# DrumPad.net
KiCad netlist of a schematic drawn in Altium Designer
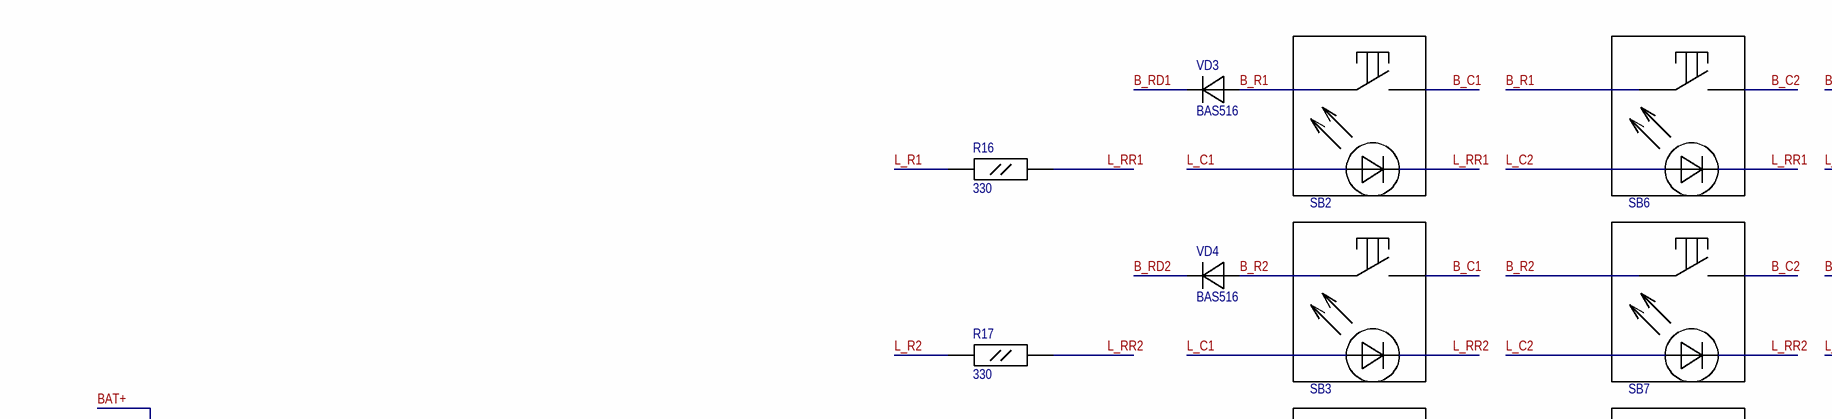
[diagram p0: DrumPad.SchDoc, top left]
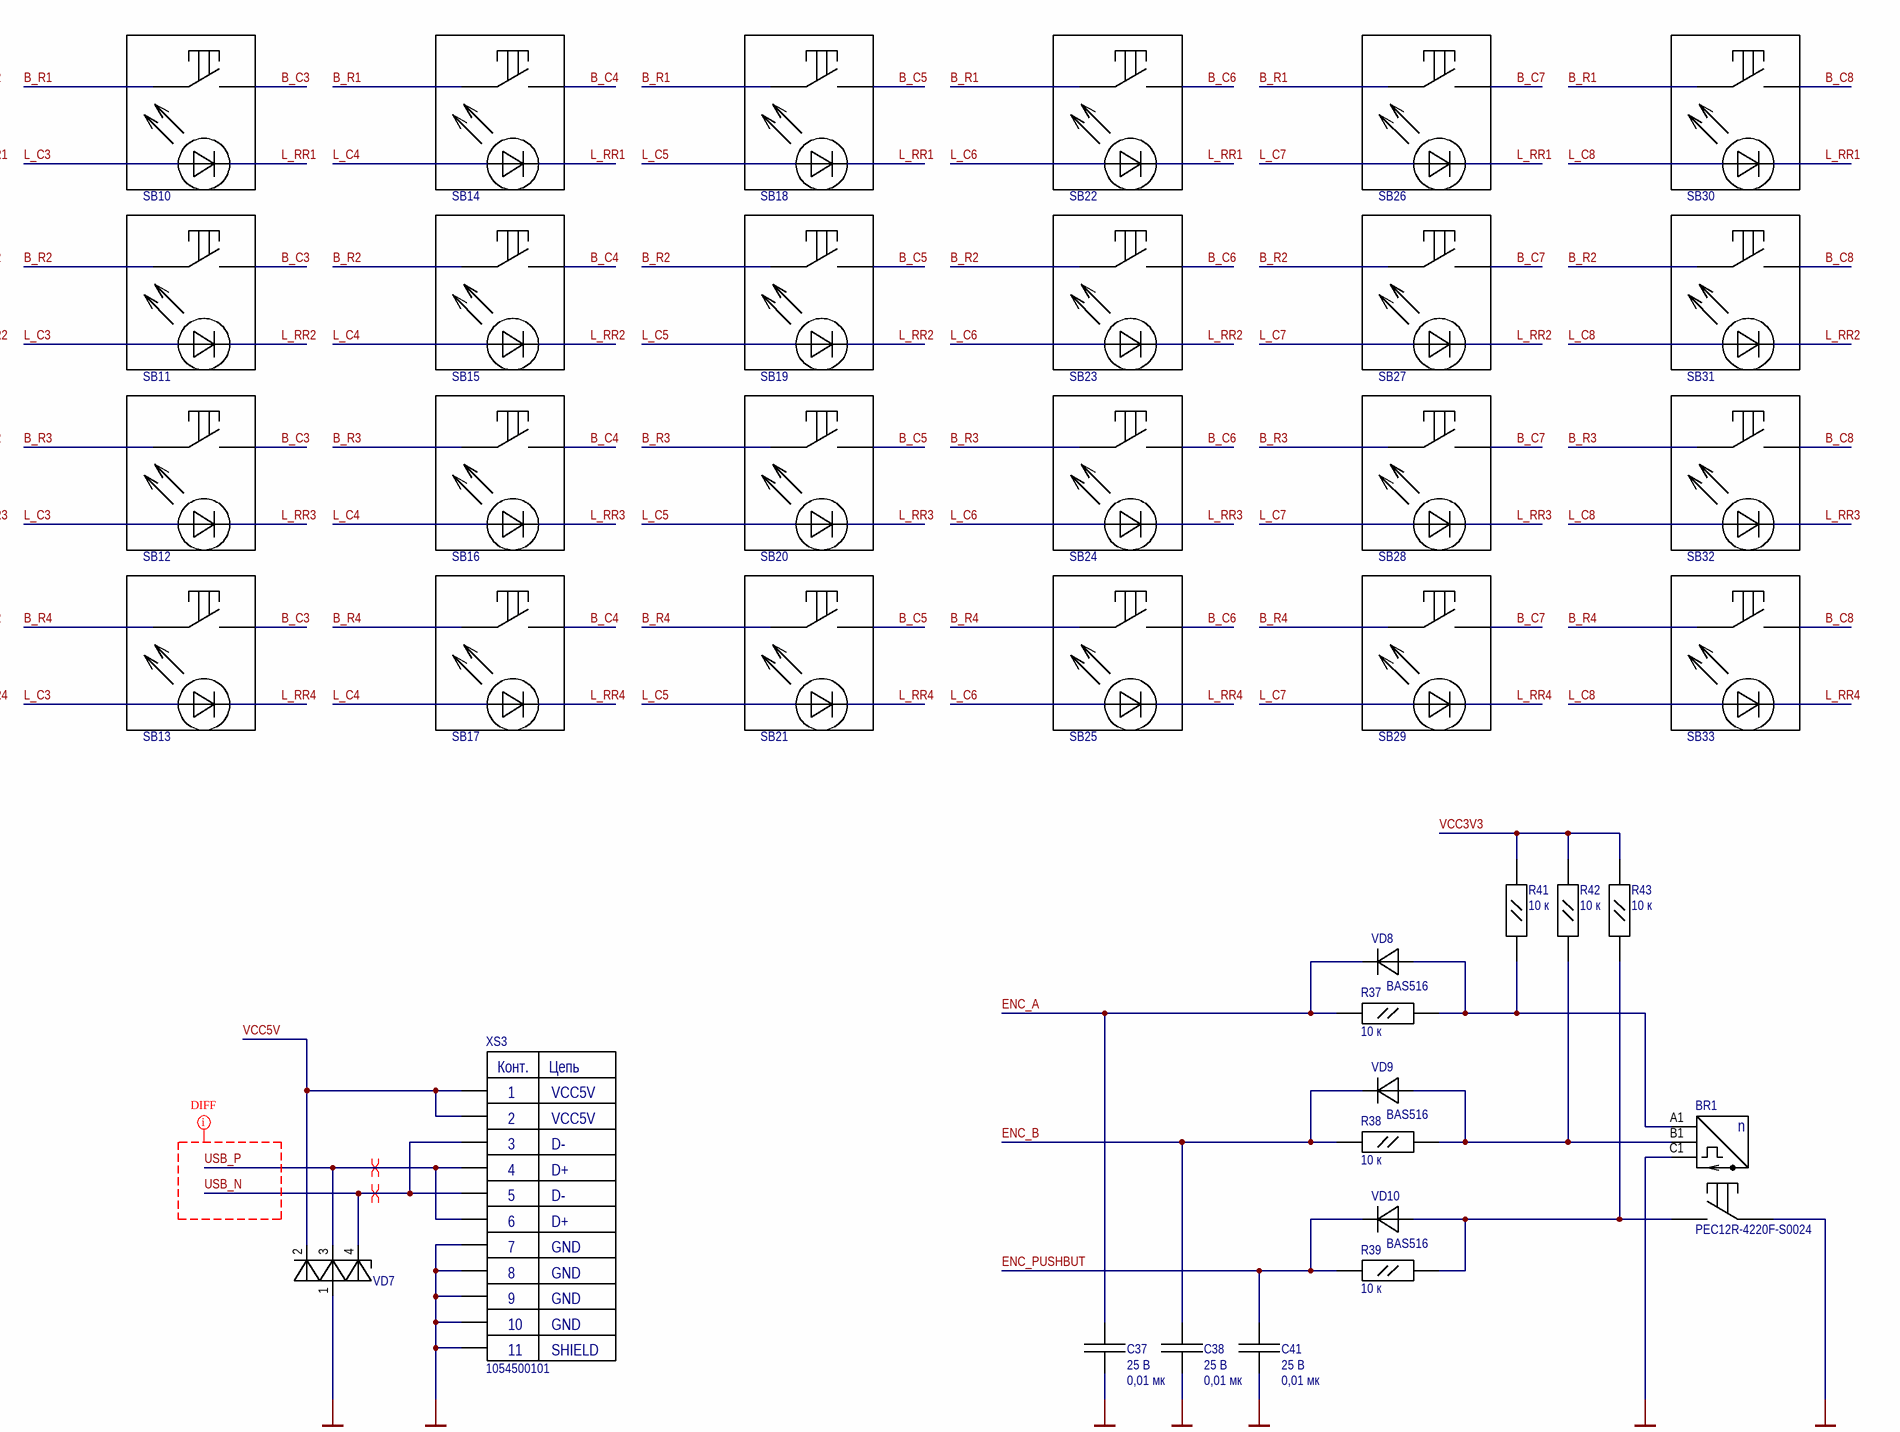
[diagram p1: DrumPad.SchDoc, top right]
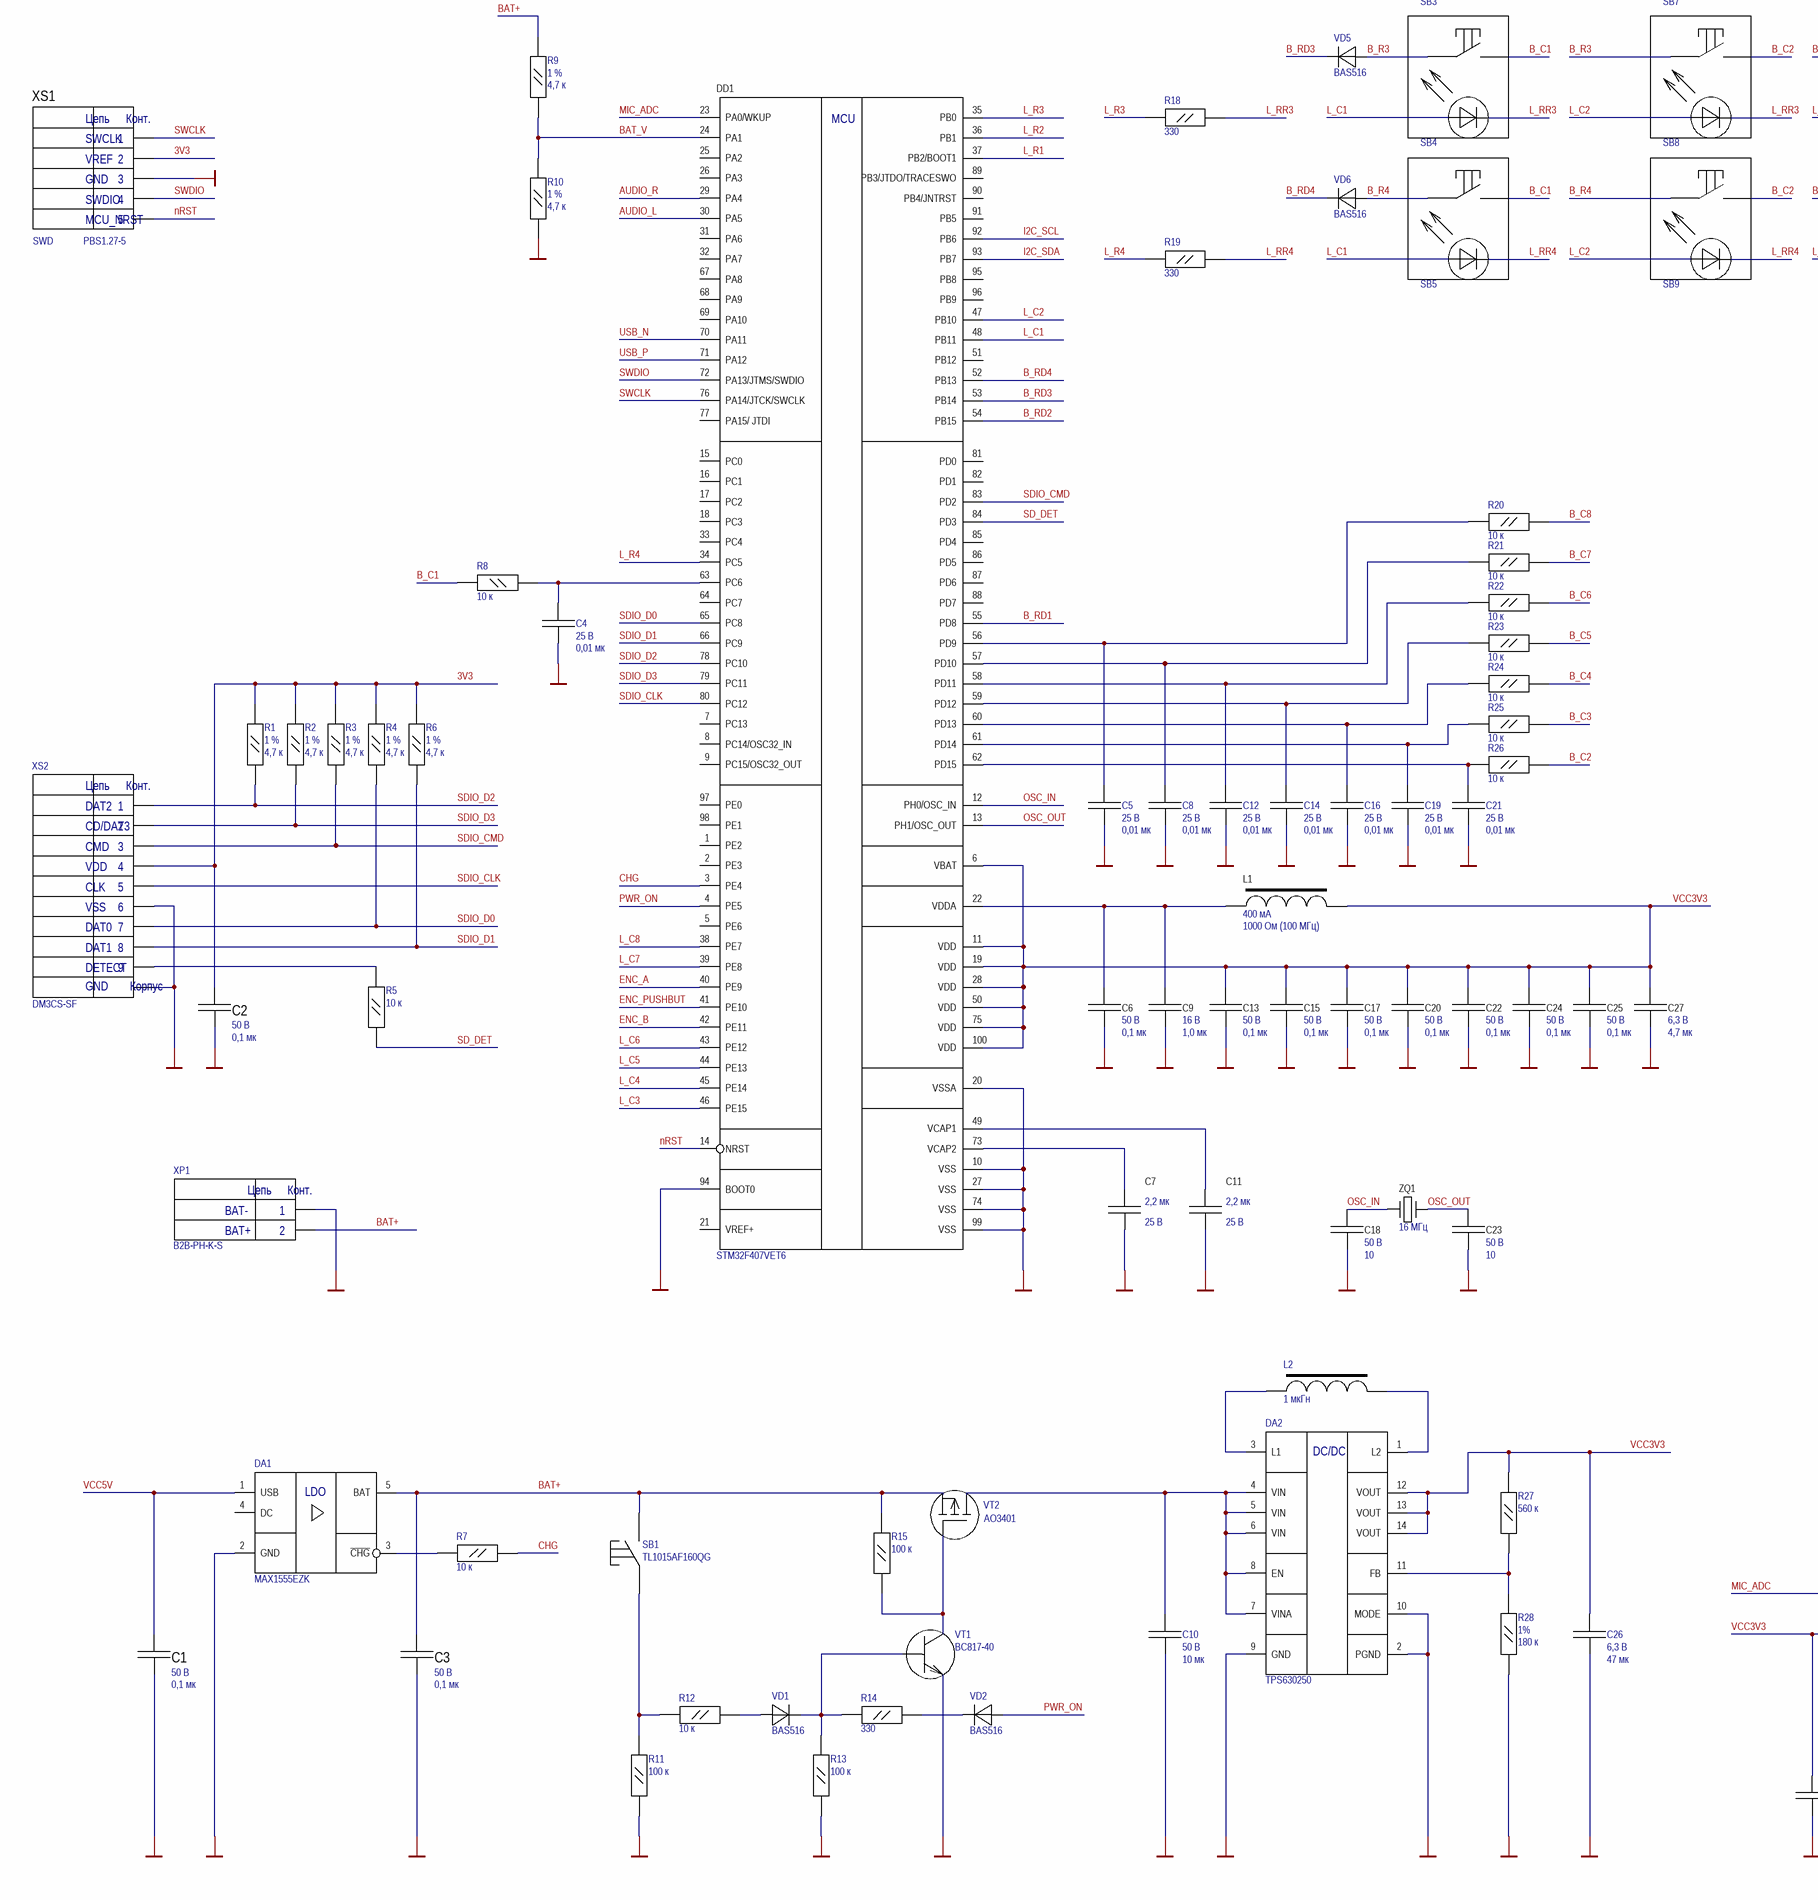
[diagram p2: DrumPad.SchDoc, bottom left]
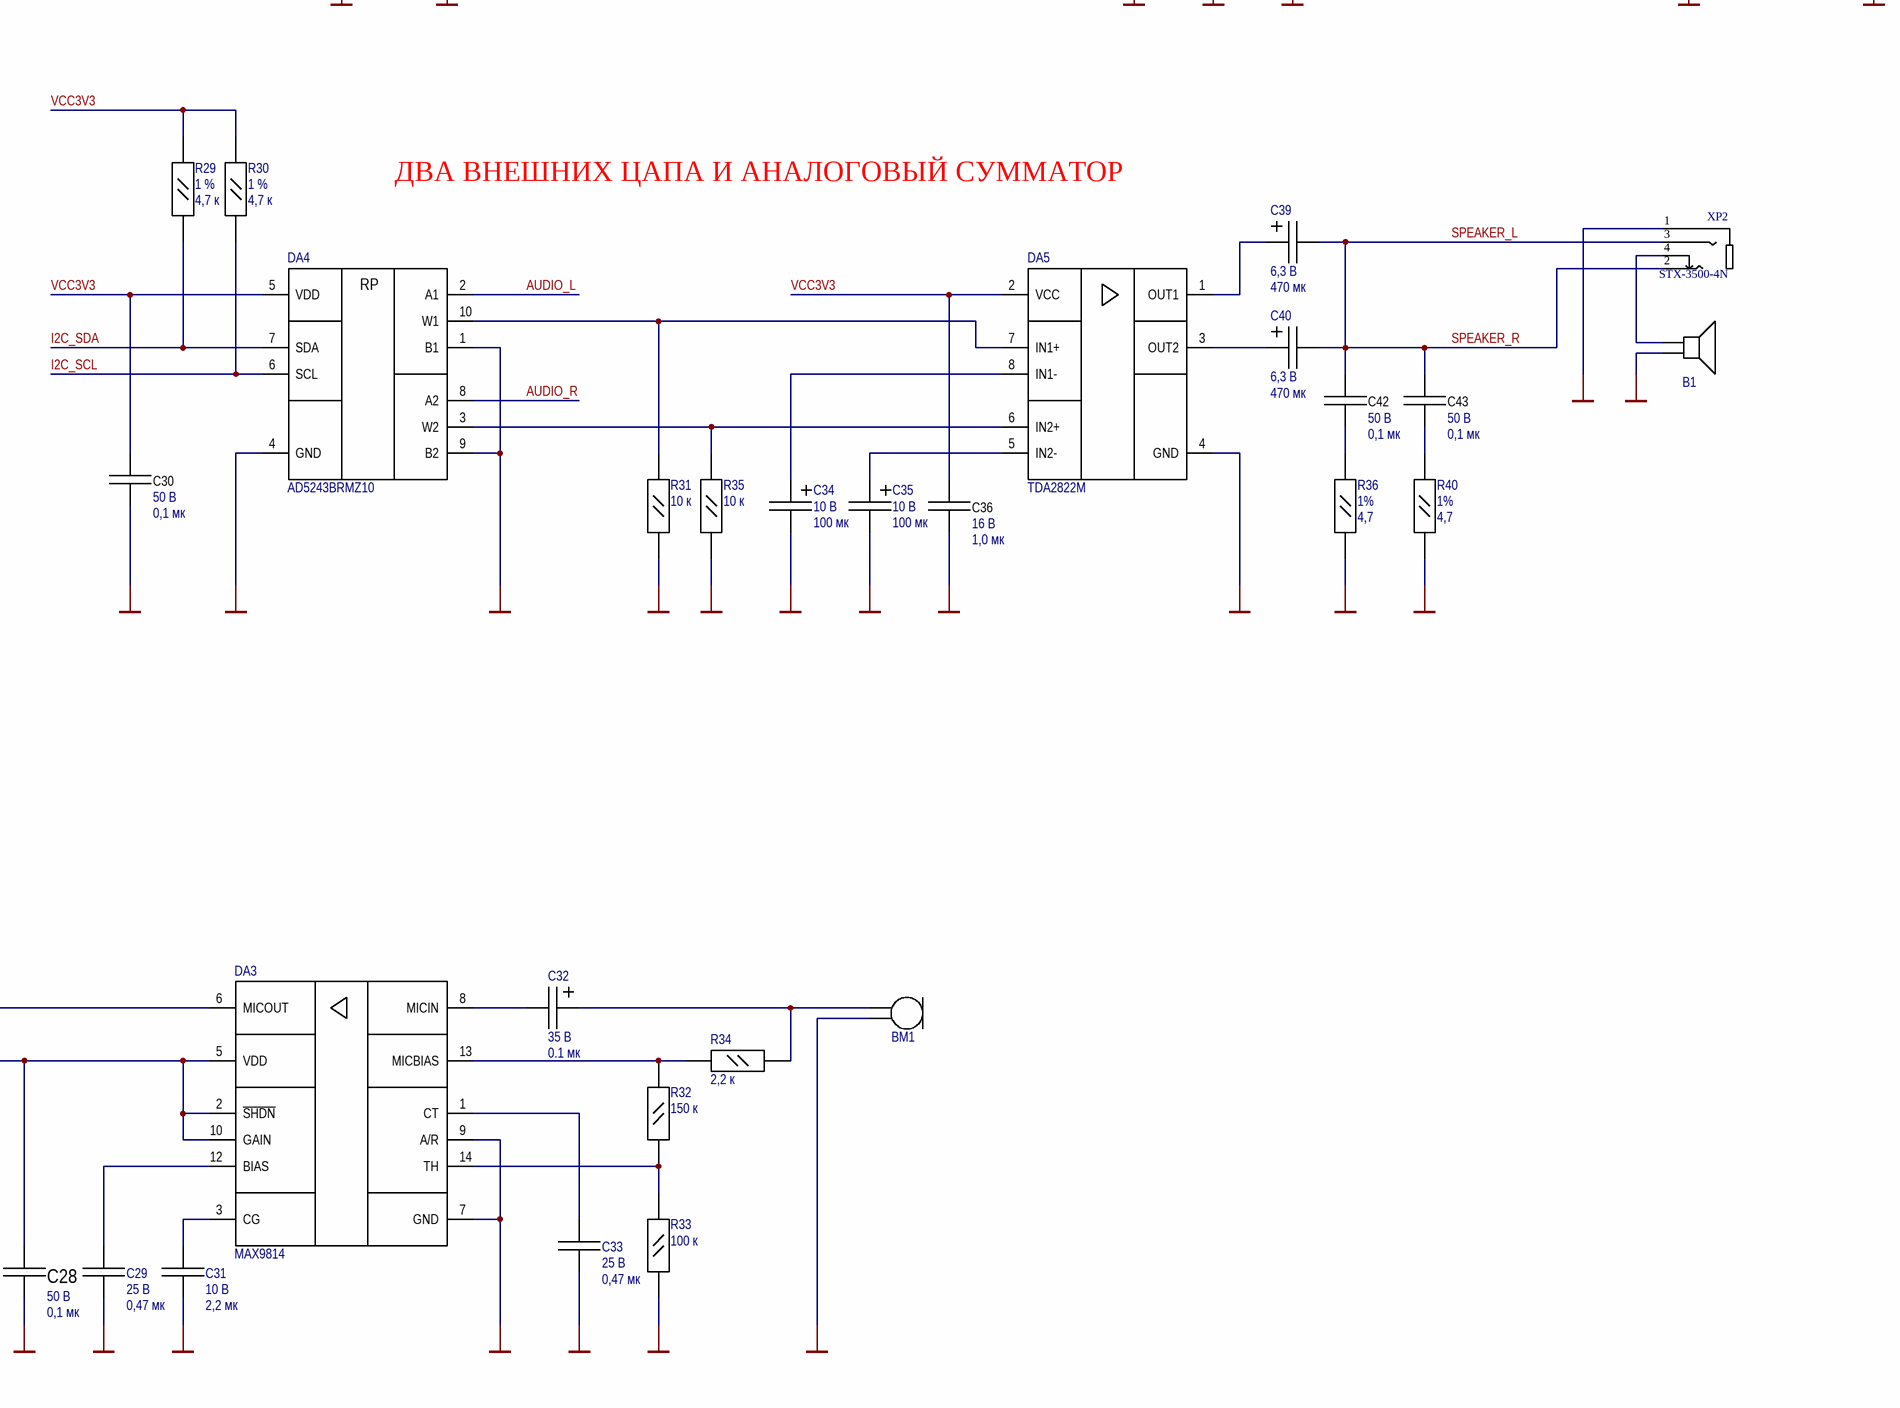
[diagram p3: DrumPad.SchDoc, bottom right]

(export (version "E")
  (design (tool "Eeschema 10.0.6"))
  (components
    (comp (ref "B1")
      (value "Speaker")
      (footprint "Speaker 20mm")
      (description "Динамик")
      (libsource (lib "altium-lib") (part "Speaker"))
    )
    (comp (ref "BM1")
      (value "EM-9767")
      (footprint "EM-9767")
      (description "Микрофон")
      (fields (field (name "VOLTAGE") "4,5 В"))
      (libsource (lib "altium-lib") (part "EM-9767"))
    )
    (comp (ref "BR1")
      (value "PEC12R-4220F-S0024")
      (footprint "PEC12R4220FS0024")
      (description "Encoder")
      (fields (field (name "MANUFACTURER") "/Укажите компанию-производителя/"))
      (libsource (lib "altium-lib") (part "PEC12R-4220F-S0024"))
    )
    (comp (ref "C1")
      (value "0,1 мк")
      (footprint "C_0603_Manual_mount")
      (description "Surface-mount Ceramic Multilayer Capacitor")
      (fields
        (field (name "TOLERANCE") "10 %")
        (field (name "MANUFACTURER") "YAGEO")
        (field (name "RATED VOLTAGE") "50 В")
      )
      (libsource (lib "altium-lib") (part "CC0603KRX7R9BB104"))
    )
    (comp (ref "C2")
      (value "0,1 мк")
      (footprint "C_0603_Manual_mount")
      (description "Surface-mount Ceramic Multilayer Capacitor")
      (fields
        (field (name "TOLERANCE") "10 %")
        (field (name "MANUFACTURER") "YAGEO")
        (field (name "RATED VOLTAGE") "50 В")
      )
      (libsource (lib "altium-lib") (part "CC0603KRX7R9BB104"))
    )
    (comp (ref "C3")
      (value "0,1 мк")
      (footprint "C_0603_Manual_mount")
      (description "Surface-mount Ceramic Multilayer Capacitor")
      (fields
        (field (name "TOLERANCE") "10 %")
        (field (name "MANUFACTURER") "YAGEO")
        (field (name "RATED VOLTAGE") "50 В")
      )
      (libsource (lib "altium-lib") (part "CC0603KRX7R9BB104"))
    )
    (comp (ref "C4")
      (value "0,01 мк")
      (footprint "C_0603_Manual_mount")
      (description "Surface-mount Ceramic Multilayer Capacitor")
      (fields
        (field (name "TOLERANCE") "10 %")
        (field (name "MANUFACTURER") "YAGEO")
        (field (name "RATED VOLTAGE") "25 В")
      )
      (libsource (lib "altium-lib") (part "CC0603KRX7R8BB103"))
    )
    (comp (ref "C5")
      (value "0,01 мк")
      (footprint "C_0603_Manual_mount")
      (description "Surface-mount Ceramic Multilayer Capacitor")
      (fields
        (field (name "TOLERANCE") "10 %")
        (field (name "MANUFACTURER") "YAGEO")
        (field (name "RATED VOLTAGE") "25 В")
      )
      (libsource (lib "altium-lib") (part "CC0603KRX7R8BB103"))
    )
    (comp (ref "C6")
      (value "0,1 мк")
      (footprint "C_0603_Manual_mount")
      (description "Surface-mount Ceramic Multilayer Capacitor")
      (fields
        (field (name "TOLERANCE") "10 %")
        (field (name "MANUFACTURER") "YAGEO")
        (field (name "RATED VOLTAGE") "50 В")
      )
      (libsource (lib "altium-lib") (part "CC0603KRX7R9BB104"))
    )
    (comp (ref "C7")
      (value "2,2 мк")
      (footprint "C_0603_Manual_mount")
      (description "Chip Monolithic Ceramic Capacitor")
      (fields
        (field (name "TOLERANCE") "0,1")
        (field (name "MANUFACTURER") "Murata Manufacturing")
        (field (name "RATED VOLTAGE") "25 В")
      )
      (libsource (lib "altium-lib") (part "GRM188R61E225KA12"))
    )
    (comp (ref "C8")
      (value "0,01 мк")
      (footprint "C_0603_Manual_mount")
      (description "Surface-mount Ceramic Multilayer Capacitor")
      (fields
        (field (name "TOLERANCE") "10 %")
        (field (name "MANUFACTURER") "YAGEO")
        (field (name "RATED VOLTAGE") "25 В")
      )
      (libsource (lib "altium-lib") (part "CC0603KRX7R8BB103"))
    )
    (comp (ref "C9")
      (value "1,0 мк")
      (footprint "C_0603_Manual_mount")
      (description "Chip Monolithic Ceramic Capacitor")
      (fields
        (field (name "TOLERANCE") "0,1")
        (field (name "MANUFACTURER") "Murata Manufacturing")
        (field (name "RATED VOLTAGE") "16 В")
      )
      (libsource (lib "altium-lib") (part "GRM188R61C105KA93"))
    )
    (comp (ref "C10")
      (value "10 мк")
      (footprint "C_1210_Manual_mount")
      (description "Chip Monolithic Ceramic Capacitor")
      (fields
        (field (name "TOLERANCE") "0,2")
        (field (name "MANUFACTURER") "Murata Manufacturing")
        (field (name "RATED VOLTAGE") "50 В")
      )
      (libsource (lib "altium-lib") (part "GRM32ER61H106MA12"))
    )
    (comp (ref "C11")
      (value "2,2 мк")
      (footprint "C_0603_Manual_mount")
      (description "Chip Monolithic Ceramic Capacitor")
      (fields
        (field (name "TOLERANCE") "0,1")
        (field (name "MANUFACTURER") "Murata Manufacturing")
        (field (name "RATED VOLTAGE") "25 В")
      )
      (libsource (lib "altium-lib") (part "GRM188R61E225KA12"))
    )
    (comp (ref "C12")
      (value "0,01 мк")
      (footprint "C_0603_Manual_mount")
      (description "Surface-mount Ceramic Multilayer Capacitor")
      (fields
        (field (name "TOLERANCE") "10 %")
        (field (name "MANUFACTURER") "YAGEO")
        (field (name "RATED VOLTAGE") "25 В")
      )
      (libsource (lib "altium-lib") (part "CC0603KRX7R8BB103"))
    )
    (comp (ref "C13")
      (value "0,1 мк")
      (footprint "C_0603_Manual_mount")
      (description "Surface-mount Ceramic Multilayer Capacitor")
      (fields
        (field (name "TOLERANCE") "10 %")
        (field (name "MANUFACTURER") "YAGEO")
        (field (name "RATED VOLTAGE") "50 В")
      )
      (libsource (lib "altium-lib") (part "CC0603KRX7R9BB104"))
    )
    (comp (ref "C14")
      (value "0,01 мк")
      (footprint "C_0603_Manual_mount")
      (description "Surface-mount Ceramic Multilayer Capacitor")
      (fields
        (field (name "TOLERANCE") "10 %")
        (field (name "MANUFACTURER") "YAGEO")
        (field (name "RATED VOLTAGE") "25 В")
      )
      (libsource (lib "altium-lib") (part "CC0603KRX7R8BB103"))
    )
    (comp (ref "C15")
      (value "0,1 мк")
      (footprint "C_0603_Manual_mount")
      (description "Surface-mount Ceramic Multilayer Capacitor")
      (fields
        (field (name "TOLERANCE") "10 %")
        (field (name "MANUFACTURER") "YAGEO")
        (field (name "RATED VOLTAGE") "50 В")
      )
      (libsource (lib "altium-lib") (part "CC0603KRX7R9BB104"))
    )
    (comp (ref "C16")
      (value "0,01 мк")
      (footprint "C_0603_Manual_mount")
      (description "Surface-mount Ceramic Multilayer Capacitor")
      (fields
        (field (name "TOLERANCE") "10 %")
        (field (name "MANUFACTURER") "YAGEO")
        (field (name "RATED VOLTAGE") "25 В")
      )
      (libsource (lib "altium-lib") (part "CC0603KRX7R8BB103"))
    )
    (comp (ref "C17")
      (value "0,1 мк")
      (footprint "C_0603_Manual_mount")
      (description "Surface-mount Ceramic Multilayer Capacitor")
      (fields
        (field (name "TOLERANCE") "10 %")
        (field (name "MANUFACTURER") "YAGEO")
        (field (name "RATED VOLTAGE") "50 В")
      )
      (libsource (lib "altium-lib") (part "CC0603KRX7R9BB104"))
    )
    (comp (ref "C18")
      (value "10")
      (footprint "C_0603_Manual_mount")
      (description "Chip Monolithic Ceramic Capacitor")
      (fields
        (field (name "TOLERANCE") "0,05")
        (field (name "MANUFACTURER") "Murata Manufacturing")
        (field (name "RATED VOLTAGE") "50 В")
      )
      (libsource (lib "altium-lib") (part "GRM1885C1H100JA01"))
    )
    (comp (ref "C19")
      (value "0,01 мк")
      (footprint "C_0603_Manual_mount")
      (description "Surface-mount Ceramic Multilayer Capacitor")
      (fields
        (field (name "TOLERANCE") "10 %")
        (field (name "MANUFACTURER") "YAGEO")
        (field (name "RATED VOLTAGE") "25 В")
      )
      (libsource (lib "altium-lib") (part "CC0603KRX7R8BB103"))
    )
    (comp (ref "C20")
      (value "0,1 мк")
      (footprint "C_0603_Manual_mount")
      (description "Surface-mount Ceramic Multilayer Capacitor")
      (fields
        (field (name "TOLERANCE") "10 %")
        (field (name "MANUFACTURER") "YAGEO")
        (field (name "RATED VOLTAGE") "50 В")
      )
      (libsource (lib "altium-lib") (part "CC0603KRX7R9BB104"))
    )
    (comp (ref "C21")
      (value "0,01 мк")
      (footprint "C_0603_Manual_mount")
      (description "Surface-mount Ceramic Multilayer Capacitor")
      (fields
        (field (name "TOLERANCE") "10 %")
        (field (name "MANUFACTURER") "YAGEO")
        (field (name "RATED VOLTAGE") "25 В")
      )
      (libsource (lib "altium-lib") (part "CC0603KRX7R8BB103"))
    )
    (comp (ref "C22")
      (value "0,1 мк")
      (footprint "C_0603_Manual_mount")
      (description "Surface-mount Ceramic Multilayer Capacitor")
      (fields
        (field (name "TOLERANCE") "10 %")
        (field (name "MANUFACTURER") "YAGEO")
        (field (name "RATED VOLTAGE") "50 В")
      )
      (libsource (lib "altium-lib") (part "CC0603KRX7R9BB104"))
    )
    (comp (ref "C23")
      (value "10")
      (footprint "C_0603_Manual_mount")
      (description "Chip Monolithic Ceramic Capacitor")
      (fields
        (field (name "TOLERANCE") "0,05")
        (field (name "MANUFACTURER") "Murata Manufacturing")
        (field (name "RATED VOLTAGE") "50 В")
      )
      (libsource (lib "altium-lib") (part "GRM1885C1H100JA01"))
    )
    (comp (ref "C24")
      (value "0,1 мк")
      (footprint "C_0603_Manual_mount")
      (description "Surface-mount Ceramic Multilayer Capacitor")
      (fields
        (field (name "TOLERANCE") "10 %")
        (field (name "MANUFACTURER") "YAGEO")
        (field (name "RATED VOLTAGE") "50 В")
      )
      (libsource (lib "altium-lib") (part "CC0603KRX7R9BB104"))
    )
    (comp (ref "C25")
      (value "0,1 мк")
      (footprint "C_0603_Manual_mount")
      (description "Surface-mount Ceramic Multilayer Capacitor")
      (fields
        (field (name "TOLERANCE") "10 %")
        (field (name "MANUFACTURER") "YAGEO")
        (field (name "RATED VOLTAGE") "50 В")
      )
      (libsource (lib "altium-lib") (part "CC0603KRX7R9BB104"))
    )
    (comp (ref "C26")
      (value "47 мк")
      (footprint "C_1210_Manual_mount")
      (description "Surface-mount Ceramic Multilayer Capacitor")
      (fields
        (field (name "TOLERANCE") "10 %")
        (field (name "MANUFACTURER") "YAGEO")
        (field (name "RATED VOLTAGE") "6,3 В")
      )
      (libsource (lib "altium-lib") (part "CC1210KRX5R5BB476"))
    )
    (comp (ref "C27")
      (value "4,7 мк")
      (footprint "C_0603_Manual_mount")
      (description "Surface-mount Ceramic Multilayer Capacitor")
      (fields
        (field (name "TOLERANCE") "10 %")
        (field (name "MANUFACTURER") "YAGEO")
        (field (name "RATED VOLTAGE") "6,3 В")
      )
      (libsource (lib "altium-lib") (part "CC0603KRX5R5BB475"))
    )
    (comp (ref "C28")
      (value "0,1 мк")
      (footprint "C_0603_Manual_mount")
      (description "Surface-mount Ceramic Multilayer Capacitor")
      (fields
        (field (name "TOLERANCE") "10 %")
        (field (name "MANUFACTURER") "YAGEO")
        (field (name "RATED VOLTAGE") "50 В")
      )
      (libsource (lib "altium-lib") (part "CC0603KRX7R9BB104"))
    )
    (comp (ref "C29")
      (value "0,47 мк")
      (footprint "C_0603_Auto_mount")
      (description "Surface-mount Ceramic Multilayer Capacitor")
      (fields
        (field (name "TOLERANCE") "10 %")
        (field (name "MANUFACTURER") "YAGEO")
        (field (name "RATED VOLTAGE") "25 В")
      )
      (libsource (lib "altium-lib") (part "CC0603KRX5R8BB474"))
    )
    (comp (ref "C30")
      (value "0,1 мк")
      (footprint "C_0603_Manual_mount")
      (description "Surface-mount Ceramic Multilayer Capacitor")
      (fields
        (field (name "TOLERANCE") "10 %")
        (field (name "MANUFACTURER") "YAGEO")
        (field (name "RATED VOLTAGE") "50 В")
      )
      (libsource (lib "altium-lib") (part "CC0603KRX7R9BB104"))
    )
    (comp (ref "C31")
      (value "2,2 мк")
      (footprint "C_0603_Auto_mount")
      (description "Chip Monolithic Ceramic Capacitor")
      (fields
        (field (name "TOLERANCE") "0,1")
        (field (name "MANUFACTURER") "Murata Manufacturing")
        (field (name "RATED VOLTAGE") "10 В")
      )
      (libsource (lib "altium-lib") (part "GRM188R61A225KE34"))
    )
    (comp (ref "C32")
      (value "0.1 мк")
      (footprint "CAPPM3216X180N")
      (description "Tantal Capacitor")
      (fields
        (field (name "TOLERANCE") "10%")
        (field (name "MANUFACTURER") "VISHAY")
        (field (name "RATED VOLTAGE") "35 B")
      )
      (libsource (lib "altium-lib") (part "293D104X9035A2TE3"))
    )
    (comp (ref "C33")
      (value "0,47 мк")
      (footprint "C_0603_Auto_mount")
      (description "Surface-mount Ceramic Multilayer Capacitor")
      (fields
        (field (name "TOLERANCE") "10 %")
        (field (name "MANUFACTURER") "YAGEO")
        (field (name "RATED VOLTAGE") "25 В")
      )
      (libsource (lib "altium-lib") (part "CC0603KRX5R8BB474"))
    )
    (comp (ref "C34")
      (value "100 мк")
      (footprint "C_Tan_C_Manual_mount")
      (description "Solid Tantalum Surface Mount Chip Capacitor, TANTAMOUNT, Molded Case, Low ESR")
      (fields
        (field (name "TOLERANCE") "10%")
        (field (name "MANUFACTURER") "VISHAY")
        (field (name "RATED VOLTAGE") "10 В")
      )
      (libsource (lib "altium-lib") (part "TR3C107K010C0100"))
    )
    (comp (ref "C35")
      (value "100 мк")
      (footprint "C_Tan_C_Manual_mount")
      (description "Solid Tantalum Surface Mount Chip Capacitor, TANTAMOUNT, Molded Case, Low ESR")
      (fields
        (field (name "TOLERANCE") "10%")
        (field (name "MANUFACTURER") "VISHAY")
        (field (name "RATED VOLTAGE") "10 В")
      )
      (libsource (lib "altium-lib") (part "TR3C107K010C0100"))
    )
    (comp (ref "C36")
      (value "1,0 мк")
      (footprint "C_0603_Manual_mount")
      (description "Chip Monolithic Ceramic Capacitor")
      (fields
        (field (name "TOLERANCE") "0,1")
        (field (name "MANUFACTURER") "Murata Manufacturing")
        (field (name "RATED VOLTAGE") "16 В")
      )
      (libsource (lib "altium-lib") (part "GRM188R61C105KA93"))
    )
    (comp (ref "C37")
      (value "0,01 мк")
      (footprint "C_0603_Manual_mount")
      (description "Surface-mount Ceramic Multilayer Capacitor")
      (fields
        (field (name "TOLERANCE") "10 %")
        (field (name "MANUFACTURER") "YAGEO")
        (field (name "RATED VOLTAGE") "25 В")
      )
      (libsource (lib "altium-lib") (part "CC0603KRX7R8BB103"))
    )
    (comp (ref "C38")
      (value "0,01 мк")
      (footprint "C_0603_Manual_mount")
      (description "Surface-mount Ceramic Multilayer Capacitor")
      (fields
        (field (name "TOLERANCE") "10 %")
        (field (name "MANUFACTURER") "YAGEO")
        (field (name "RATED VOLTAGE") "25 В")
      )
      (libsource (lib "altium-lib") (part "CC0603KRX7R8BB103"))
    )
    (comp (ref "C39")
      (value "470 мк")
      (footprint "T495D")
      (description "Tantal Capacitor")
      (fields
        (field (name "TOLERANCE") "10%")
        (field (name "MANUFACTURER") "KEMET")
        (field (name "RATED VOLTAGE") "6,3 B")
      )
      (libsource (lib "altium-lib") (part "T495D477K006ATE100"))
    )
    (comp (ref "C40")
      (value "470 мк")
      (footprint "T495D")
      (description "Tantal Capacitor")
      (fields
        (field (name "TOLERANCE") "10%")
        (field (name "MANUFACTURER") "KEMET")
        (field (name "RATED VOLTAGE") "6,3 B")
      )
      (libsource (lib "altium-lib") (part "T495D477K006ATE100"))
    )
    (comp (ref "C41")
      (value "0,01 мк")
      (footprint "C_0603_Manual_mount")
      (description "Surface-mount Ceramic Multilayer Capacitor")
      (fields
        (field (name "TOLERANCE") "10 %")
        (field (name "MANUFACTURER") "YAGEO")
        (field (name "RATED VOLTAGE") "25 В")
      )
      (libsource (lib "altium-lib") (part "CC0603KRX7R8BB103"))
    )
    (comp (ref "C42")
      (value "0,1 мк")
      (footprint "C_0603_Manual_mount")
      (description "Surface-mount Ceramic Multilayer Capacitor")
      (fields
        (field (name "TOLERANCE") "10 %")
        (field (name "MANUFACTURER") "YAGEO")
        (field (name "RATED VOLTAGE") "50 В")
      )
      (libsource (lib "altium-lib") (part "CC0603KRX7R9BB104"))
    )
    (comp (ref "C43")
      (value "0,1 мк")
      (footprint "C_0603_Manual_mount")
      (description "Surface-mount Ceramic Multilayer Capacitor")
      (fields
        (field (name "TOLERANCE") "10 %")
        (field (name "MANUFACTURER") "YAGEO")
        (field (name "RATED VOLTAGE") "50 В")
      )
      (libsource (lib "altium-lib") (part "CC0603KRX7R9BB104"))
    )
    (comp (ref "DA1")
      (value "MAX1555EZK")
      (footprint "SOT-23-5")
      (description "1S Li-Po/Li-Ion charger")
      (fields (field (name "MANUFACTURER") "maxim integrated"))
      (libsource (lib "altium-lib") (part "MAX1555EZK"))
    )
    (comp (ref "DA2")
      (value "TPS630250")
      (footprint "VQFN-14")
      (description "High efficiency, low quiescent current buck-boost converter")
      (fields (field (name "MANUFACTURER") "TI"))
      (libsource (lib "altium-lib") (part "TPS630250"))
    )
    (comp (ref "DA3")
      (value "MAX9814")
      (footprint "TDFN-14-EP")
      (description "Microphone audio power amplifier")
      (fields (field (name "MANUFACTURER") "Maxim"))
      (libsource (lib "altium-lib") (part "MAX9814"))
    )
    (comp (ref "DA4")
      (value "AD5243BRMZ10")
      (footprint "smd-active:MSOP-10")
      (description "2-channel, 256-position potentiometers")
      (fields (field (name "MANUFACTURER") "Analog Devices"))
      (libsource (lib "Solovev") (part "AD5243BRMZ10"))
    )
    (comp (ref "DA5")
      (value "TDA2822M")
      (footprint "SO-8")
      (description "Dual audio power amplifier")
      (fields (field (name "MANUFACTURER") "ST"))
      (libsource (lib "altium-lib") (part "TDA2822M"))
    )
    (comp (ref "DD1")
      (value "STM32F407VET6")
      (footprint "LQFP-100")
      (fields (field (name "MANUFACTURER") "STMicroelectronics"))
      (libsource (lib "altium-lib") (part "STM32F407VET6"))
    )
    (comp (ref "L1")
      (value "1000 Ом (100 МГц)")
      (footprint "FB_0603_Auto_mount")
      (description "Chip Ferrite Bead")
      (fields
        (field (name "TOLERANCE") "25%")
        (field (name "MANUFACTURER") "Murata Manufacturing")
        (field (name "RATED CURRENT") "400 мА")
      )
      (libsource (lib "altium-lib") (part "BLM18AG102SN1"))
    )
    (comp (ref "L2")
      (value "1 мкГн")
      (footprint "SRR4028")
      (description "Shielded Power Inductor")
      (fields (field (name "TOLERANCE") "20%") (field (name "MANUFACTURER") "TDK"))
      (libsource (lib "altium-lib") (part "SPM4020T-1R0M-LR"))
    )
    (comp (ref "R1")
      (value "4,7 к")
      (footprint "R_0603_Manual_mount")
      (description "General Purpose Chip Resistor")
      (fields
        (field (name "MANUFACTURER") "YAGEO")
        (field (name "TOLERANCE") "1 %")
        (field (name "PART NUMBER") "RC0603FR-074K7L")
      )
      (libsource (lib "passive") (part "Resistor_0.125W_tol"))
    )
    (comp (ref "R2")
      (value "4,7 к")
      (footprint "R_0603_Manual_mount")
      (description "General Purpose Chip Resistor")
      (fields
        (field (name "MANUFACTURER") "YAGEO")
        (field (name "TOLERANCE") "1 %")
        (field (name "PART NUMBER") "RC0603FR-074K7L")
      )
      (libsource (lib "passive") (part "Resistor_0.125W_tol"))
    )
    (comp (ref "R3")
      (value "4,7 к")
      (footprint "R_0603_Manual_mount")
      (description "General Purpose Chip Resistor")
      (fields
        (field (name "MANUFACTURER") "YAGEO")
        (field (name "TOLERANCE") "1 %")
        (field (name "PART NUMBER") "RC0603FR-074K7L")
      )
      (libsource (lib "passive") (part "Resistor_0.125W_tol"))
    )
    (comp (ref "R4")
      (value "4,7 к")
      (footprint "R_0603_Manual_mount")
      (description "General Purpose Chip Resistor")
      (fields
        (field (name "MANUFACTURER") "YAGEO")
        (field (name "TOLERANCE") "1 %")
        (field (name "PART NUMBER") "RC0603FR-074K7L")
      )
      (libsource (lib "passive") (part "Resistor_0.125W_tol"))
    )
    (comp (ref "R5")
      (value "10 к")
      (footprint "R_0603_Manual_mount")
      (description "General Purpose Chip Resistor")
      (fields (field (name "TOLERANCE") "5 %") (field (name "MANUFACTURER") "YAGEO"))
      (libsource (lib "altium-lib") (part "RC0603JR-0710KL"))
    )
    (comp (ref "R6")
      (value "4,7 к")
      (footprint "R_0603_Manual_mount")
      (description "General Purpose Chip Resistor")
      (fields
        (field (name "MANUFACTURER") "YAGEO")
        (field (name "TOLERANCE") "1 %")
        (field (name "PART NUMBER") "RC0603FR-074K7L")
      )
      (libsource (lib "passive") (part "Resistor_0.125W_tol"))
    )
    (comp (ref "R7")
      (value "10 к")
      (footprint "R_0603_Manual_mount")
      (description "General Purpose Chip Resistor")
      (fields (field (name "TOLERANCE") "5 %") (field (name "MANUFACTURER") "YAGEO"))
      (libsource (lib "altium-lib") (part "RC0603JR-0710KL"))
    )
    (comp (ref "R8")
      (value "10 к")
      (footprint "R_0603_Manual_mount")
      (description "General Purpose Chip Resistor")
      (fields (field (name "TOLERANCE") "5 %") (field (name "MANUFACTURER") "YAGEO"))
      (libsource (lib "altium-lib") (part "RC0603JR-0710KL"))
    )
    (comp (ref "R9")
      (value "4,7 к")
      (footprint "R_0603_Manual_mount")
      (description "General Purpose Chip Resistor")
      (fields
        (field (name "MANUFACTURER") "YAGEO")
        (field (name "TOLERANCE") "1 %")
        (field (name "PART NUMBER") "RC0603FR-074K7L")
      )
      (libsource (lib "passive") (part "Resistor_0.125W_tol"))
    )
    (comp (ref "R10")
      (value "4,7 к")
      (footprint "R_0603_Manual_mount")
      (description "General Purpose Chip Resistor")
      (fields
        (field (name "MANUFACTURER") "YAGEO")
        (field (name "TOLERANCE") "1 %")
        (field (name "PART NUMBER") "RC0603FR-074K7L")
      )
      (libsource (lib "passive") (part "Resistor_0.125W_tol"))
    )
    (comp (ref "R11")
      (value "100 к")
      (footprint "R_0603_Manual_mount")
      (description "General Purpose Chip Resistor")
      (fields (field (name "TOLERANCE") "5 %") (field (name "MANUFACTURER") "YAGEO"))
      (libsource (lib "altium-lib") (part "RC0603JR-07100KL"))
    )
    (comp (ref "R12")
      (value "10 к")
      (footprint "R_0603_Manual_mount")
      (description "General Purpose Chip Resistor")
      (fields (field (name "TOLERANCE") "5 %") (field (name "MANUFACTURER") "YAGEO"))
      (libsource (lib "altium-lib") (part "RC0603JR-0710KL"))
    )
    (comp (ref "R13")
      (value "100 к")
      (footprint "R_0603_Manual_mount")
      (description "General Purpose Chip Resistor")
      (fields (field (name "TOLERANCE") "5 %") (field (name "MANUFACTURER") "YAGEO"))
      (libsource (lib "altium-lib") (part "RC0603JR-07100KL"))
    )
    (comp (ref "R14")
      (value "330")
      (footprint "R_0603_Manual_mount")
      (description "General Purpose Chip Resistor")
      (fields (field (name "TOLERANCE") "5 %") (field (name "MANUFACTURER") "YAGEO"))
      (libsource (lib "altium-lib") (part "RC0603JR-07330RL"))
    )
    (comp (ref "R15")
      (value "100 к")
      (footprint "R_0603_Manual_mount")
      (description "General Purpose Chip Resistor")
      (fields (field (name "TOLERANCE") "5 %") (field (name "MANUFACTURER") "YAGEO"))
      (libsource (lib "altium-lib") (part "RC0603JR-07100KL"))
    )
    (comp (ref "R16")
      (value "330")
      (footprint "R_0603_Manual_mount")
      (description "General Purpose Chip Resistor")
      (fields (field (name "TOLERANCE") "5 %") (field (name "MANUFACTURER") "YAGEO"))
      (libsource (lib "altium-lib") (part "RC0603JR-07330RL"))
    )
    (comp (ref "R17")
      (value "330")
      (footprint "R_0603_Manual_mount")
      (description "General Purpose Chip Resistor")
      (fields (field (name "TOLERANCE") "5 %") (field (name "MANUFACTURER") "YAGEO"))
      (libsource (lib "altium-lib") (part "RC0603JR-07330RL"))
    )
    (comp (ref "R18")
      (value "330")
      (footprint "R_0603_Manual_mount")
      (description "General Purpose Chip Resistor")
      (fields (field (name "TOLERANCE") "5 %") (field (name "MANUFACTURER") "YAGEO"))
      (libsource (lib "altium-lib") (part "RC0603JR-07330RL"))
    )
    (comp (ref "R19")
      (value "330")
      (footprint "R_0603_Manual_mount")
      (description "General Purpose Chip Resistor")
      (fields (field (name "TOLERANCE") "5 %") (field (name "MANUFACTURER") "YAGEO"))
      (libsource (lib "altium-lib") (part "RC0603JR-07330RL"))
    )
    (comp (ref "R20")
      (value "10 к")
      (footprint "R_0603_Manual_mount")
      (description "General Purpose Chip Resistor")
      (fields (field (name "TOLERANCE") "5 %") (field (name "MANUFACTURER") "YAGEO"))
      (libsource (lib "altium-lib") (part "RC0603JR-0710KL"))
    )
    (comp (ref "R21")
      (value "10 к")
      (footprint "R_0603_Manual_mount")
      (description "General Purpose Chip Resistor")
      (fields (field (name "TOLERANCE") "5 %") (field (name "MANUFACTURER") "YAGEO"))
      (libsource (lib "altium-lib") (part "RC0603JR-0710KL"))
    )
    (comp (ref "R22")
      (value "10 к")
      (footprint "R_0603_Manual_mount")
      (description "General Purpose Chip Resistor")
      (fields (field (name "TOLERANCE") "5 %") (field (name "MANUFACTURER") "YAGEO"))
      (libsource (lib "altium-lib") (part "RC0603JR-0710KL"))
    )
    (comp (ref "R23")
      (value "10 к")
      (footprint "R_0603_Manual_mount")
      (description "General Purpose Chip Resistor")
      (fields (field (name "TOLERANCE") "5 %") (field (name "MANUFACTURER") "YAGEO"))
      (libsource (lib "altium-lib") (part "RC0603JR-0710KL"))
    )
    (comp (ref "R24")
      (value "10 к")
      (footprint "R_0603_Manual_mount")
      (description "General Purpose Chip Resistor")
      (fields (field (name "TOLERANCE") "5 %") (field (name "MANUFACTURER") "YAGEO"))
      (libsource (lib "altium-lib") (part "RC0603JR-0710KL"))
    )
    (comp (ref "R25")
      (value "10 к")
      (footprint "R_0603_Manual_mount")
      (description "General Purpose Chip Resistor")
      (fields (field (name "TOLERANCE") "5 %") (field (name "MANUFACTURER") "YAGEO"))
      (libsource (lib "altium-lib") (part "RC0603JR-0710KL"))
    )
    (comp (ref "R26")
      (value "10 к")
      (footprint "R_0603_Manual_mount")
      (description "General Purpose Chip Resistor")
      (fields (field (name "TOLERANCE") "5 %") (field (name "MANUFACTURER") "YAGEO"))
      (libsource (lib "altium-lib") (part "RC0603JR-0710KL"))
    )
    (comp (ref "R27")
      (value "560 к")
      (footprint "R_0603_Auto_mount")
      (description "General Purpose Chip Resistor")
      (fields (field (name "TOLERANCE") "5 %") (field (name "MANUFACTURER") "YAGEO"))
      (libsource (lib "altium-lib") (part "RC0603JR-07560KL"))
    )
    (comp (ref "R28")
      (value "180 к")
      (footprint "R_0603_Auto_mount")
      (description "General Purpose Chip Resistor")
      (fields
        (field (name "MANUFACTURER") "YAGEO")
        (field (name "TOLERANCE") "1%")
        (field (name "Comment") "RC0603FR-07180KL")
      )
      (libsource (lib "altium-lib") (part "RC0603FR-07180KL"))
    )
    (comp (ref "R29")
      (value "4,7 к")
      (footprint "R_0603_Manual_mount")
      (description "General Purpose Chip Resistor")
      (fields
        (field (name "MANUFACTURER") "YAGEO")
        (field (name "TOLERANCE") "1 %")
        (field (name "PART NUMBER") "RC0603FR-074K7L")
      )
      (libsource (lib "passive") (part "Resistor_0.125W_tol"))
    )
    (comp (ref "R30")
      (value "4,7 к")
      (footprint "R_0603_Manual_mount")
      (description "General Purpose Chip Resistor")
      (fields
        (field (name "MANUFACTURER") "YAGEO")
        (field (name "TOLERANCE") "1 %")
        (field (name "PART NUMBER") "RC0603FR-074K7L")
      )
      (libsource (lib "passive") (part "Resistor_0.125W_tol"))
    )
    (comp (ref "R31")
      (value "10 к")
      (footprint "R_0603_Manual_mount")
      (description "General Purpose Chip Resistor")
      (fields (field (name "TOLERANCE") "5 %") (field (name "MANUFACTURER") "YAGEO"))
      (libsource (lib "altium-lib") (part "RC0603JR-0710KL"))
    )
    (comp (ref "R32")
      (value "150 к")
      (footprint "R_0603_Manual_mount")
      (description "General Purpose Chip Resistor")
      (fields (field (name "TOLERANCE") "5 %") (field (name "MANUFACTURER") "YAGEO"))
      (libsource (lib "altium-lib") (part "RC0603JR-07150KL"))
    )
    (comp (ref "R33")
      (value "100 к")
      (footprint "R_0603_Auto_mount")
      (description "General Purpose Chip Resistor")
      (fields (field (name "TOLERANCE") "5 %") (field (name "MANUFACTURER") "YAGEO"))
      (libsource (lib "altium-lib") (part "RC0603JR-07100KL"))
    )
    (comp (ref "R34")
      (value "2,2 к")
      (footprint "R_0603_Manual_mount")
      (description "General Purpose Chip Resistor")
      (fields (field (name "TOLERANCE") "5 %") (field (name "MANUFACTURER") "YAGEO"))
      (libsource (lib "altium-lib") (part "RC0603JR-072K2L"))
    )
    (comp (ref "R35")
      (value "10 к")
      (footprint "R_0603_Manual_mount")
      (description "General Purpose Chip Resistor")
      (fields (field (name "TOLERANCE") "5 %") (field (name "MANUFACTURER") "YAGEO"))
      (libsource (lib "altium-lib") (part "RC0603JR-0710KL"))
    )
    (comp (ref "R36")
      (value "4,7")
      (footprint "R_0603_Manual_mount")
      (description "General Purpose Chip Resistor")
      (fields
        (field (name "MANUFACTURER") "YAGEO")
        (field (name "TOLERANCE") "1%")
        (field (name "Comment") "RC0603FR-074R7L")
      )
      (libsource (lib "altium-lib") (part "RC0603FR-074R7L"))
    )
    (comp (ref "R37")
      (value "10 к")
      (footprint "R_0603_Manual_mount")
      (description "General Purpose Chip Resistor")
      (fields (field (name "TOLERANCE") "5 %") (field (name "MANUFACTURER") "YAGEO"))
      (libsource (lib "altium-lib") (part "RC0603JR-0710KL"))
    )
    (comp (ref "R38")
      (value "10 к")
      (footprint "R_0603_Manual_mount")
      (description "General Purpose Chip Resistor")
      (fields (field (name "TOLERANCE") "5 %") (field (name "MANUFACTURER") "YAGEO"))
      (libsource (lib "altium-lib") (part "RC0603JR-0710KL"))
    )
    (comp (ref "R39")
      (value "10 к")
      (footprint "R_0603_Manual_mount")
      (description "General Purpose Chip Resistor")
      (fields (field (name "TOLERANCE") "5 %") (field (name "MANUFACTURER") "YAGEO"))
      (libsource (lib "altium-lib") (part "RC0603JR-0710KL"))
    )
    (comp (ref "R40")
      (value "4,7")
      (footprint "R_0603_Manual_mount")
      (description "General Purpose Chip Resistor")
      (fields
        (field (name "MANUFACTURER") "YAGEO")
        (field (name "TOLERANCE") "1%")
        (field (name "Comment") "RC0603FR-074R7L")
      )
      (libsource (lib "altium-lib") (part "RC0603FR-074R7L"))
    )
    (comp (ref "R41")
      (value "10 к")
      (footprint "R_0603_Manual_mount")
      (description "General Purpose Chip Resistor")
      (fields (field (name "TOLERANCE") "5 %") (field (name "MANUFACTURER") "YAGEO"))
      (libsource (lib "altium-lib") (part "RC0603JR-0710KL"))
    )
    (comp (ref "R42")
      (value "10 к")
      (footprint "R_0603_Manual_mount")
      (description "General Purpose Chip Resistor")
      (fields (field (name "TOLERANCE") "5 %") (field (name "MANUFACTURER") "YAGEO"))
      (libsource (lib "altium-lib") (part "RC0603JR-0710KL"))
    )
    (comp (ref "R43")
      (value "10 к")
      (footprint "R_0603_Manual_mount")
      (description "General Purpose Chip Resistor")
      (fields (field (name "TOLERANCE") "5 %") (field (name "MANUFACTURER") "YAGEO"))
      (libsource (lib "altium-lib") (part "RC0603JR-0710KL"))
    )
    (comp (ref "SB1")
      (value "TL1015AF160QG")
      (footprint "TL1015AF160QG")
      (description "SMD pushbutton")
      (fields (field (name "MANUFACTURER") "E-SWITCH"))
      (libsource (lib "altium-lib") (part "TL1015AF160QG"))
    )
    (comp (ref "SB2")
      (value "Led_button")
      (footprint "Led_button")
      (description "Кнопка с встроенным светодиодом")
      (fields (field (name "MANUFACTURER") "NONAME"))
      (libsource (lib "altium-lib") (part "Led_button"))
    )
    (comp (ref "SB3")
      (value "Led_button")
      (footprint "Led_button")
      (description "Кнопка с встроенным светодиодом")
      (fields (field (name "MANUFACTURER") "NONAME"))
      (libsource (lib "altium-lib") (part "Led_button"))
    )
    (comp (ref "SB4")
      (value "Led_button")
      (footprint "Led_button")
      (description "Кнопка с встроенным светодиодом")
      (fields (field (name "MANUFACTURER") "NONAME"))
      (libsource (lib "altium-lib") (part "Led_button"))
    )
    (comp (ref "SB5")
      (value "Led_button")
      (footprint "Led_button")
      (description "Кнопка с встроенным светодиодом")
      (fields (field (name "MANUFACTURER") "NONAME"))
      (libsource (lib "altium-lib") (part "Led_button"))
    )
    (comp (ref "SB6")
      (value "Led_button")
      (footprint "Led_button")
      (description "Кнопка с встроенным светодиодом")
      (fields (field (name "MANUFACTURER") "NONAME"))
      (libsource (lib "altium-lib") (part "Led_button"))
    )
    (comp (ref "SB7")
      (value "Led_button")
      (footprint "Led_button")
      (description "Кнопка с встроенным светодиодом")
      (fields (field (name "MANUFACTURER") "NONAME"))
      (libsource (lib "altium-lib") (part "Led_button"))
    )
    (comp (ref "SB8")
      (value "Led_button")
      (footprint "Led_button")
      (description "Кнопка с встроенным светодиодом")
      (fields (field (name "MANUFACTURER") "NONAME"))
      (libsource (lib "altium-lib") (part "Led_button"))
    )
    (comp (ref "SB9")
      (value "Led_button")
      (footprint "Led_button")
      (description "Кнопка с встроенным светодиодом")
      (fields (field (name "MANUFACTURER") "NONAME"))
      (libsource (lib "altium-lib") (part "Led_button"))
    )
    (comp (ref "SB10")
      (value "Led_button")
      (footprint "Led_button")
      (description "Кнопка с встроенным светодиодом")
      (fields (field (name "MANUFACTURER") "NONAME"))
      (libsource (lib "altium-lib") (part "Led_button"))
    )
    (comp (ref "SB11")
      (value "Led_button")
      (footprint "Led_button")
      (description "Кнопка с встроенным светодиодом")
      (fields (field (name "MANUFACTURER") "NONAME"))
      (libsource (lib "altium-lib") (part "Led_button"))
    )
    (comp (ref "SB12")
      (value "Led_button")
      (footprint "Led_button")
      (description "Кнопка с встроенным светодиодом")
      (fields (field (name "MANUFACTURER") "NONAME"))
      (libsource (lib "altium-lib") (part "Led_button"))
    )
    (comp (ref "SB13")
      (value "Led_button")
      (footprint "Led_button")
      (description "Кнопка с встроенным светодиодом")
      (fields (field (name "MANUFACTURER") "NONAME"))
      (libsource (lib "altium-lib") (part "Led_button"))
    )
    (comp (ref "SB14")
      (value "Led_button")
      (footprint "Led_button")
      (description "Кнопка с встроенным светодиодом")
      (fields (field (name "MANUFACTURER") "NONAME"))
      (libsource (lib "altium-lib") (part "Led_button"))
    )
    (comp (ref "SB15")
      (value "Led_button")
      (footprint "Led_button")
      (description "Кнопка с встроенным светодиодом")
      (fields (field (name "MANUFACTURER") "NONAME"))
      (libsource (lib "altium-lib") (part "Led_button"))
    )
    (comp (ref "SB16")
      (value "Led_button")
      (footprint "Led_button")
      (description "Кнопка с встроенным светодиодом")
      (fields (field (name "MANUFACTURER") "NONAME"))
      (libsource (lib "altium-lib") (part "Led_button"))
    )
    (comp (ref "SB17")
      (value "Led_button")
      (footprint "Led_button")
      (description "Кнопка с встроенным светодиодом")
      (fields (field (name "MANUFACTURER") "NONAME"))
      (libsource (lib "altium-lib") (part "Led_button"))
    )
    (comp (ref "SB18")
      (value "Led_button")
      (footprint "Led_button")
      (description "Кнопка с встроенным светодиодом")
      (fields (field (name "MANUFACTURER") "NONAME"))
      (libsource (lib "altium-lib") (part "Led_button"))
    )
    (comp (ref "SB19")
      (value "Led_button")
      (footprint "Led_button")
      (description "Кнопка с встроенным светодиодом")
      (fields (field (name "MANUFACTURER") "NONAME"))
      (libsource (lib "altium-lib") (part "Led_button"))
    )
    (comp (ref "SB20")
      (value "Led_button")
      (footprint "Led_button")
      (description "Кнопка с встроенным светодиодом")
      (fields (field (name "MANUFACTURER") "NONAME"))
      (libsource (lib "altium-lib") (part "Led_button"))
    )
    (comp (ref "SB21")
      (value "Led_button")
      (footprint "Led_button")
      (description "Кнопка с встроенным светодиодом")
      (fields (field (name "MANUFACTURER") "NONAME"))
      (libsource (lib "altium-lib") (part "Led_button"))
    )
    (comp (ref "SB22")
      (value "Led_button")
      (footprint "Led_button")
      (description "Кнопка с встроенным светодиодом")
      (fields (field (name "MANUFACTURER") "NONAME"))
      (libsource (lib "altium-lib") (part "Led_button"))
    )
    (comp (ref "SB23")
      (value "Led_button")
      (footprint "Led_button")
      (description "Кнопка с встроенным светодиодом")
      (fields (field (name "MANUFACTURER") "NONAME"))
      (libsource (lib "altium-lib") (part "Led_button"))
    )
    (comp (ref "SB24")
      (value "Led_button")
      (footprint "Led_button")
      (description "Кнопка с встроенным светодиодом")
      (fields (field (name "MANUFACTURER") "NONAME"))
      (libsource (lib "altium-lib") (part "Led_button"))
    )
    (comp (ref "SB25")
      (value "Led_button")
      (footprint "Led_button")
      (description "Кнопка с встроенным светодиодом")
      (fields (field (name "MANUFACTURER") "NONAME"))
      (libsource (lib "altium-lib") (part "Led_button"))
    )
    (comp (ref "SB26")
      (value "Led_button")
      (footprint "Led_button")
      (description "Кнопка с встроенным светодиодом")
      (fields (field (name "MANUFACTURER") "NONAME"))
      (libsource (lib "altium-lib") (part "Led_button"))
    )
    (comp (ref "SB27")
      (value "Led_button")
      (footprint "Led_button")
      (description "Кнопка с встроенным светодиодом")
      (fields (field (name "MANUFACTURER") "NONAME"))
      (libsource (lib "altium-lib") (part "Led_button"))
    )
    (comp (ref "SB28")
      (value "Led_button")
      (footprint "Led_button")
      (description "Кнопка с встроенным светодиодом")
      (fields (field (name "MANUFACTURER") "NONAME"))
      (libsource (lib "altium-lib") (part "Led_button"))
    )
    (comp (ref "SB29")
      (value "Led_button")
      (footprint "Led_button")
      (description "Кнопка с встроенным светодиодом")
      (fields (field (name "MANUFACTURER") "NONAME"))
      (libsource (lib "altium-lib") (part "Led_button"))
    )
    (comp (ref "SB30")
      (value "Led_button")
      (footprint "Led_button")
      (description "Кнопка с встроенным светодиодом")
      (fields (field (name "MANUFACTURER") "NONAME"))
      (libsource (lib "altium-lib") (part "Led_button"))
    )
    (comp (ref "SB31")
      (value "Led_button")
      (footprint "Led_button")
      (description "Кнопка с встроенным светодиодом")
      (fields (field (name "MANUFACTURER") "NONAME"))
      (libsource (lib "altium-lib") (part "Led_button"))
    )
    (comp (ref "SB32")
      (value "Led_button")
      (footprint "Led_button")
      (description "Кнопка с встроенным светодиодом")
      (fields (field (name "MANUFACTURER") "NONAME"))
      (libsource (lib "altium-lib") (part "Led_button"))
    )
    (comp (ref "SB33")
      (value "Led_button")
      (footprint "Led_button")
      (description "Кнопка с встроенным светодиодом")
      (fields (field (name "MANUFACTURER") "NONAME"))
      (libsource (lib "altium-lib") (part "Led_button"))
    )
    (comp (ref "VD1")
      (value "BAS516")
      (footprint "SOD-523")
      (description "High-speed switching diode")
      (fields (field (name "MANUFACTURER") "NXP"))
      (libsource (lib "altium-lib") (part "BAS516"))
    )
    (comp (ref "VD2")
      (value "BAS516")
      (footprint "SOD-523")
      (description "High-speed switching diode")
      (fields (field (name "MANUFACTURER") "NXP"))
      (libsource (lib "altium-lib") (part "BAS516"))
    )
    (comp (ref "VD3")
      (value "BAS516")
      (footprint "SOD-523")
      (description "High-speed switching diode")
      (fields (field (name "MANUFACTURER") "NXP"))
      (libsource (lib "altium-lib") (part "BAS516"))
    )
    (comp (ref "VD4")
      (value "BAS516")
      (footprint "SOD-523")
      (description "High-speed switching diode")
      (fields (field (name "MANUFACTURER") "NXP"))
      (libsource (lib "altium-lib") (part "BAS516"))
    )
    (comp (ref "VD5")
      (value "BAS516")
      (footprint "SOD-523")
      (description "High-speed switching diode")
      (fields (field (name "MANUFACTURER") "NXP"))
      (libsource (lib "altium-lib") (part "BAS516"))
    )
    (comp (ref "VD6")
      (value "BAS516")
      (footprint "SOD-523")
      (description "High-speed switching diode")
      (fields (field (name "MANUFACTURER") "NXP"))
      (libsource (lib "altium-lib") (part "BAS516"))
    )
    (comp (ref "VD7")
      (value "SP0503BAHTG")
      (footprint "SOT-143-4")
      (description "30pF 30kV Unidirectional TVS Array")
      (fields (field (name "MANUFACTURER") "Littelfuse"))
      (libsource (lib "altium-lib") (part "SP0503BAHTG"))
    )
    (comp (ref "VD8")
      (value "BAS516")
      (footprint "SOD-523")
      (description "High-speed switching diode")
      (fields (field (name "MANUFACTURER") "NXP"))
      (libsource (lib "altium-lib") (part "BAS516"))
    )
    (comp (ref "VD9")
      (value "BAS516")
      (footprint "SOD-523")
      (description "High-speed switching diode")
      (fields (field (name "MANUFACTURER") "NXP"))
      (libsource (lib "altium-lib") (part "BAS516"))
    )
    (comp (ref "VD10")
      (value "BAS516")
      (footprint "SOD-523")
      (description "High-speed switching diode")
      (fields (field (name "MANUFACTURER") "NXP"))
      (libsource (lib "altium-lib") (part "BAS516"))
    )
    (comp (ref "VT1")
      (value "BC817-40")
      (footprint "SOT-23")
      (description "NPN general-purpose transistor")
      (fields (field (name "MANUFACTURER") "NXP"))
      (libsource (lib "altium-lib") (part "BC817-40"))
    )
    (comp (ref "VT2")
      (value "AO3401")
      (footprint "SOT-23")
      (description "Транзистор полевой P-канальный")
      (fields (field (name "MANUFACTURER") "Hottech"))
      (libsource (lib "altium-lib") (part "AO3401"))
    )
    (comp (ref "XP1")
      (value "B2B-PH-K-S")
      (footprint "B2B-PH-K-S")
      (description "PH connector")
      (fields (field (name "MANUFACTURER") "JST"))
      (libsource (lib "altium-lib") (part "B2B-PH-K-S"))
    )
    (comp (ref "XP2")
      (value "STX-3500-4N")
      (footprint "KYCON_STX-3500-4N")
      (description "3.5 jack")
      (libsource (lib "altium-lib") (part "STX-3500-4N"))
    )
    (comp (ref "XS1")
      (value "PBS1.27-5")
      (footprint "PBS1.27-5")
      (description "PBS connector")
      (fields (field (name "MANUFACTURER") "NONAME") (field (name "INTERFACE") "SWD"))
      (libsource (lib "altium-lib") (part "SWD PBS1.27-5"))
    )
    (comp (ref "XS2")
      (value "DM3CS-SF")
      (footprint "DM3CSSF")
      (description "1.10mm Pitch TransFlash Memory Card Connector, Hinge Type, Round Corner Top")
      (fields (field (name "MANUFACTURER") "Molex"))
      (libsource (lib "altium-lib") (part "DM3CS-SF"))
    )
    (comp (ref "XS3")
      (value "1054500101")
      (footprint "MOLEX_1054500101")
      (description "Type-C connector")
      (libsource (lib "altium-lib") (part "1054500101"))
    )
    (comp (ref "ZQ1")
      (value "16 МГц")
      (footprint "NX3225SA")
      (description "QUARTZ CRYSTAL")
      (fields (field (name "MANUFACTURER") "NDK") (field (name "Comment") "NX3225SA-16.000M-STD-CRS-2"))
      (libsource (lib "altium-lib") (part "NX3225SA-16.000M-STD-CRS-2"))
    )
  )
  (nets
    (net (code "1") (name "/3V3") (class "Default")
      (node (ref "C2") (pin "1") (pinfunction "1_1") (pintype "passive"))
      (node (ref "R1") (pin "2") (pinfunction "2_2") (pintype "passive"))
      (node (ref "R2") (pin "2") (pinfunction "2_2") (pintype "passive"))
      (node (ref "R3") (pin "2") (pinfunction "2_2") (pintype "passive"))
      (node (ref "R4") (pin "2") (pinfunction "2_2") (pintype "passive"))
      (node (ref "R6") (pin "2") (pinfunction "2_2") (pintype "passive"))
      (node (ref "XS1") (pin "2") (pinfunction "2_2") (pintype "passive"))
      (node (ref "XS2") (pin "4") (pinfunction "4_4") (pintype "passive"))
    )
    (net (code "2") (name "/AUDIO_L") (class "Default")
      (node (ref "DA4") (pin "2") (pinfunction "A1_2") (pintype "passive"))
      (node (ref "DD1") (pin "30") (pinfunction "PA5_30") (pintype "passive"))
    )
    (net (code "3") (name "/AUDIO_R") (class "Default")
      (node (ref "DA4") (pin "8") (pinfunction "A2_8") (pintype "passive"))
      (node (ref "DD1") (pin "29") (pinfunction "PA4_29") (pintype "passive"))
    )
    (net (code "4") (name "/BAT+") (class "Default")
      (node (ref "C3") (pin "1") (pinfunction "1_1") (pintype "passive"))
      (node (ref "DA1") (pin "5") (pinfunction "BAT_5") (pintype "passive"))
      (node (ref "R15") (pin "2") (pinfunction "2_2") (pintype "passive"))
      (node (ref "R9") (pin "2") (pinfunction "2_2") (pintype "passive"))
      (node (ref "SB1") (pin "2") (pinfunction "2_2") (pintype "passive"))
      (node (ref "VT2") (pin "2") (pinfunction "2_2") (pintype "passive"))
      (node (ref "XP1") (pin "2") (pinfunction "2_2") (pintype "passive"))
    )
    (net (code "5") (name "/BAT_V") (class "Default")
      (node (ref "DD1") (pin "24") (pinfunction "PA1_24") (pintype "passive"))
      (node (ref "R10") (pin "2") (pinfunction "2_2") (pintype "passive"))
      (node (ref "R9") (pin "1") (pinfunction "1_1") (pintype "passive"))
    )
    (net (code "6") (name "/B_C1") (class "Default")
      (node (ref "R8") (pin "1") (pinfunction "1_1") (pintype "passive"))
      (node (ref "SB2") (pin "2") (pinfunction "2_2") (pintype "passive"))
      (node (ref "SB3") (pin "2") (pinfunction "2_2") (pintype "passive"))
      (node (ref "SB4") (pin "2") (pinfunction "2_2") (pintype "passive"))
      (node (ref "SB5") (pin "2") (pinfunction "2_2") (pintype "passive"))
    )
    (net (code "7") (name "/B_C2") (class "Default")
      (node (ref "R26") (pin "1") (pinfunction "1_1") (pintype "passive"))
      (node (ref "SB6") (pin "2") (pinfunction "2_2") (pintype "passive"))
      (node (ref "SB7") (pin "2") (pinfunction "2_2") (pintype "passive"))
      (node (ref "SB8") (pin "2") (pinfunction "2_2") (pintype "passive"))
      (node (ref "SB9") (pin "2") (pinfunction "2_2") (pintype "passive"))
    )
    (net (code "8") (name "/B_C3") (class "Default")
      (node (ref "R25") (pin "1") (pinfunction "1_1") (pintype "passive"))
      (node (ref "SB10") (pin "2") (pinfunction "2_2") (pintype "passive"))
      (node (ref "SB11") (pin "2") (pinfunction "2_2") (pintype "passive"))
      (node (ref "SB12") (pin "2") (pinfunction "2_2") (pintype "passive"))
      (node (ref "SB13") (pin "2") (pinfunction "2_2") (pintype "passive"))
    )
    (net (code "9") (name "/B_C4") (class "Default")
      (node (ref "R24") (pin "1") (pinfunction "1_1") (pintype "passive"))
      (node (ref "SB14") (pin "2") (pinfunction "2_2") (pintype "passive"))
      (node (ref "SB15") (pin "2") (pinfunction "2_2") (pintype "passive"))
      (node (ref "SB16") (pin "2") (pinfunction "2_2") (pintype "passive"))
      (node (ref "SB17") (pin "2") (pinfunction "2_2") (pintype "passive"))
    )
    (net (code "10") (name "/B_C5") (class "Default")
      (node (ref "R23") (pin "1") (pinfunction "1_1") (pintype "passive"))
      (node (ref "SB18") (pin "2") (pinfunction "2_2") (pintype "passive"))
      (node (ref "SB19") (pin "2") (pinfunction "2_2") (pintype "passive"))
      (node (ref "SB20") (pin "2") (pinfunction "2_2") (pintype "passive"))
      (node (ref "SB21") (pin "2") (pinfunction "2_2") (pintype "passive"))
    )
    (net (code "11") (name "/B_C6") (class "Default")
      (node (ref "R22") (pin "1") (pinfunction "1_1") (pintype "passive"))
      (node (ref "SB22") (pin "2") (pinfunction "2_2") (pintype "passive"))
      (node (ref "SB23") (pin "2") (pinfunction "2_2") (pintype "passive"))
      (node (ref "SB24") (pin "2") (pinfunction "2_2") (pintype "passive"))
      (node (ref "SB25") (pin "2") (pinfunction "2_2") (pintype "passive"))
    )
    (net (code "12") (name "/B_C7") (class "Default")
      (node (ref "R21") (pin "1") (pinfunction "1_1") (pintype "passive"))
      (node (ref "SB26") (pin "2") (pinfunction "2_2") (pintype "passive"))
      (node (ref "SB27") (pin "2") (pinfunction "2_2") (pintype "passive"))
      (node (ref "SB28") (pin "2") (pinfunction "2_2") (pintype "passive"))
      (node (ref "SB29") (pin "2") (pinfunction "2_2") (pintype "passive"))
    )
    (net (code "13") (name "/B_C8") (class "Default")
      (node (ref "R20") (pin "1") (pinfunction "1_1") (pintype "passive"))
      (node (ref "SB30") (pin "2") (pinfunction "2_2") (pintype "passive"))
      (node (ref "SB31") (pin "2") (pinfunction "2_2") (pintype "passive"))
      (node (ref "SB32") (pin "2") (pinfunction "2_2") (pintype "passive"))
      (node (ref "SB33") (pin "2") (pinfunction "2_2") (pintype "passive"))
    )
    (net (code "14") (name "/B_R1") (class "Default")
      (node (ref "SB10") (pin "1") (pinfunction "1_1") (pintype "passive"))
      (node (ref "SB14") (pin "1") (pinfunction "1_1") (pintype "passive"))
      (node (ref "SB18") (pin "1") (pinfunction "1_1") (pintype "passive"))
      (node (ref "SB2") (pin "1") (pinfunction "1_1") (pintype "passive"))
      (node (ref "SB22") (pin "1") (pinfunction "1_1") (pintype "passive"))
      (node (ref "SB26") (pin "1") (pinfunction "1_1") (pintype "passive"))
      (node (ref "SB30") (pin "1") (pinfunction "1_1") (pintype "passive"))
      (node (ref "SB6") (pin "1") (pinfunction "1_1") (pintype "passive"))
      (node (ref "VD3") (pin "A") (pinfunction "A_A") (pintype "passive"))
    )
    (net (code "15") (name "/B_R2") (class "Default")
      (node (ref "SB11") (pin "1") (pinfunction "1_1") (pintype "passive"))
      (node (ref "SB15") (pin "1") (pinfunction "1_1") (pintype "passive"))
      (node (ref "SB19") (pin "1") (pinfunction "1_1") (pintype "passive"))
      (node (ref "SB23") (pin "1") (pinfunction "1_1") (pintype "passive"))
      (node (ref "SB27") (pin "1") (pinfunction "1_1") (pintype "passive"))
      (node (ref "SB3") (pin "1") (pinfunction "1_1") (pintype "passive"))
      (node (ref "SB31") (pin "1") (pinfunction "1_1") (pintype "passive"))
      (node (ref "SB7") (pin "1") (pinfunction "1_1") (pintype "passive"))
      (node (ref "VD4") (pin "A") (pinfunction "A_A") (pintype "passive"))
    )
    (net (code "16") (name "/B_R3") (class "Default")
      (node (ref "SB12") (pin "1") (pinfunction "1_1") (pintype "passive"))
      (node (ref "SB16") (pin "1") (pinfunction "1_1") (pintype "passive"))
      (node (ref "SB20") (pin "1") (pinfunction "1_1") (pintype "passive"))
      (node (ref "SB24") (pin "1") (pinfunction "1_1") (pintype "passive"))
      (node (ref "SB28") (pin "1") (pinfunction "1_1") (pintype "passive"))
      (node (ref "SB32") (pin "1") (pinfunction "1_1") (pintype "passive"))
      (node (ref "SB4") (pin "1") (pinfunction "1_1") (pintype "passive"))
      (node (ref "SB8") (pin "1") (pinfunction "1_1") (pintype "passive"))
      (node (ref "VD5") (pin "A") (pinfunction "A_A") (pintype "passive"))
    )
    (net (code "17") (name "/B_R4") (class "Default")
      (node (ref "SB13") (pin "1") (pinfunction "1_1") (pintype "passive"))
      (node (ref "SB17") (pin "1") (pinfunction "1_1") (pintype "passive"))
      (node (ref "SB21") (pin "1") (pinfunction "1_1") (pintype "passive"))
      (node (ref "SB25") (pin "1") (pinfunction "1_1") (pintype "passive"))
      (node (ref "SB29") (pin "1") (pinfunction "1_1") (pintype "passive"))
      (node (ref "SB33") (pin "1") (pinfunction "1_1") (pintype "passive"))
      (node (ref "SB5") (pin "1") (pinfunction "1_1") (pintype "passive"))
      (node (ref "SB9") (pin "1") (pinfunction "1_1") (pintype "passive"))
      (node (ref "VD6") (pin "A") (pinfunction "A_A") (pintype "passive"))
    )
    (net (code "18") (name "/B_RD1") (class "Default")
      (node (ref "DD1") (pin "55") (pinfunction "PD8_55") (pintype "passive"))
      (node (ref "VD3") (pin "C") (pinfunction "C_C") (pintype "passive"))
    )
    (net (code "19") (name "/B_RD2") (class "Default")
      (node (ref "DD1") (pin "54") (pinfunction "PB15_54") (pintype "passive"))
      (node (ref "VD4") (pin "C") (pinfunction "C_C") (pintype "passive"))
    )
    (net (code "20") (name "/B_RD3") (class "Default")
      (node (ref "DD1") (pin "53") (pinfunction "PB14_53") (pintype "passive"))
      (node (ref "VD5") (pin "C") (pinfunction "C_C") (pintype "passive"))
    )
    (net (code "21") (name "/B_RD4") (class "Default")
      (node (ref "DD1") (pin "52") (pinfunction "PB13_52") (pintype "passive"))
      (node (ref "VD6") (pin "C") (pinfunction "C_C") (pintype "passive"))
    )
    (net (code "22") (name "/CHG") (class "Default")
      (node (ref "DD1") (pin "3") (pinfunction "PE4_3") (pintype "passive"))
      (node (ref "R7") (pin "1") (pinfunction "1_1") (pintype "passive"))
    )
    (net (code "23") (name "/ENC_A") (class "Default")
      (node (ref "C37") (pin "1") (pinfunction "1_1") (pintype "passive"))
      (node (ref "DD1") (pin "40") (pinfunction "PE9_40") (pintype "passive"))
      (node (ref "R37") (pin "1") (pinfunction "1_1") (pintype "passive"))
      (node (ref "VD8") (pin "C") (pinfunction "C_C") (pintype "passive"))
    )
    (net (code "24") (name "/ENC_B") (class "Default")
      (node (ref "C38") (pin "1") (pinfunction "1_1") (pintype "passive"))
      (node (ref "DD1") (pin "42") (pinfunction "PE11_42") (pintype "passive"))
      (node (ref "R38") (pin "1") (pinfunction "1_1") (pintype "passive"))
      (node (ref "VD9") (pin "C") (pinfunction "C_C") (pintype "passive"))
    )
    (net (code "25") (name "/ENC_PUSHBUT") (class "Default")
      (node (ref "C41") (pin "1") (pinfunction "1_1") (pintype "passive"))
      (node (ref "DD1") (pin "41") (pinfunction "PE10_41") (pintype "passive"))
      (node (ref "R39") (pin "1") (pinfunction "1_1") (pintype "passive"))
      (node (ref "VD10") (pin "C") (pinfunction "C_C") (pintype "passive"))
    )
    (net (code "26") (name "/I2C_SCL") (class "Default")
      (node (ref "DA4") (pin "6") (pinfunction "SCL_6") (pintype "passive"))
      (node (ref "DD1") (pin "92") (pinfunction "PB6_92") (pintype "passive"))
      (node (ref "R30") (pin "1") (pinfunction "1_1") (pintype "passive"))
    )
    (net (code "27") (name "/I2C_SDA") (class "Default")
      (node (ref "DA4") (pin "7") (pinfunction "SDA_7") (pintype "passive"))
      (node (ref "DD1") (pin "93") (pinfunction "PB7_93") (pintype "passive"))
      (node (ref "R29") (pin "1") (pinfunction "1_1") (pintype "passive"))
    )
    (net (code "28") (name "/L_C1") (class "Default")
      (node (ref "DD1") (pin "48") (pinfunction "PB11_48") (pintype "passive"))
      (node (ref "SB2") (pin "3") (pinfunction "3_3") (pintype "passive"))
      (node (ref "SB3") (pin "3") (pinfunction "3_3") (pintype "passive"))
      (node (ref "SB4") (pin "3") (pinfunction "3_3") (pintype "passive"))
      (node (ref "SB5") (pin "3") (pinfunction "3_3") (pintype "passive"))
    )
    (net (code "29") (name "/L_C2") (class "Default")
      (node (ref "DD1") (pin "47") (pinfunction "PB10_47") (pintype "passive"))
      (node (ref "SB6") (pin "3") (pinfunction "3_3") (pintype "passive"))
      (node (ref "SB7") (pin "3") (pinfunction "3_3") (pintype "passive"))
      (node (ref "SB8") (pin "3") (pinfunction "3_3") (pintype "passive"))
      (node (ref "SB9") (pin "3") (pinfunction "3_3") (pintype "passive"))
    )
    (net (code "30") (name "/L_C3") (class "Default")
      (node (ref "DD1") (pin "46") (pinfunction "PE15_46") (pintype "passive"))
      (node (ref "SB10") (pin "3") (pinfunction "3_3") (pintype "passive"))
      (node (ref "SB11") (pin "3") (pinfunction "3_3") (pintype "passive"))
      (node (ref "SB12") (pin "3") (pinfunction "3_3") (pintype "passive"))
      (node (ref "SB13") (pin "3") (pinfunction "3_3") (pintype "passive"))
    )
    (net (code "31") (name "/L_C4") (class "Default")
      (node (ref "DD1") (pin "45") (pinfunction "PE14_45") (pintype "passive"))
      (node (ref "SB14") (pin "3") (pinfunction "3_3") (pintype "passive"))
      (node (ref "SB15") (pin "3") (pinfunction "3_3") (pintype "passive"))
      (node (ref "SB16") (pin "3") (pinfunction "3_3") (pintype "passive"))
      (node (ref "SB17") (pin "3") (pinfunction "3_3") (pintype "passive"))
    )
    (net (code "32") (name "/L_C5") (class "Default")
      (node (ref "DD1") (pin "44") (pinfunction "PE13_44") (pintype "passive"))
      (node (ref "SB18") (pin "3") (pinfunction "3_3") (pintype "passive"))
      (node (ref "SB19") (pin "3") (pinfunction "3_3") (pintype "passive"))
      (node (ref "SB20") (pin "3") (pinfunction "3_3") (pintype "passive"))
      (node (ref "SB21") (pin "3") (pinfunction "3_3") (pintype "passive"))
    )
    (net (code "33") (name "/L_C6") (class "Default")
      (node (ref "DD1") (pin "43") (pinfunction "PE12_43") (pintype "passive"))
      (node (ref "SB22") (pin "3") (pinfunction "3_3") (pintype "passive"))
      (node (ref "SB23") (pin "3") (pinfunction "3_3") (pintype "passive"))
      (node (ref "SB24") (pin "3") (pinfunction "3_3") (pintype "passive"))
      (node (ref "SB25") (pin "3") (pinfunction "3_3") (pintype "passive"))
    )
    (net (code "34") (name "/L_C7") (class "Default")
      (node (ref "DD1") (pin "39") (pinfunction "PE8_39") (pintype "passive"))
      (node (ref "SB26") (pin "3") (pinfunction "3_3") (pintype "passive"))
      (node (ref "SB27") (pin "3") (pinfunction "3_3") (pintype "passive"))
      (node (ref "SB28") (pin "3") (pinfunction "3_3") (pintype "passive"))
      (node (ref "SB29") (pin "3") (pinfunction "3_3") (pintype "passive"))
    )
    (net (code "35") (name "/L_C8") (class "Default")
      (node (ref "DD1") (pin "38") (pinfunction "PE7_38") (pintype "passive"))
      (node (ref "SB30") (pin "3") (pinfunction "3_3") (pintype "passive"))
      (node (ref "SB31") (pin "3") (pinfunction "3_3") (pintype "passive"))
      (node (ref "SB32") (pin "3") (pinfunction "3_3") (pintype "passive"))
      (node (ref "SB33") (pin "3") (pinfunction "3_3") (pintype "passive"))
    )
    (net (code "36") (name "/L_R1") (class "Default")
      (node (ref "DD1") (pin "37") (pinfunction "PB2/BOOT1_37") (pintype "passive"))
      (node (ref "R16") (pin "1") (pinfunction "1_1") (pintype "passive"))
    )
    (net (code "37") (name "/L_R2") (class "Default")
      (node (ref "DD1") (pin "36") (pinfunction "PB1_36") (pintype "passive"))
      (node (ref "R17") (pin "1") (pinfunction "1_1") (pintype "passive"))
    )
    (net (code "38") (name "/L_R3") (class "Default")
      (node (ref "DD1") (pin "35") (pinfunction "PB0_35") (pintype "passive"))
      (node (ref "R18") (pin "1") (pinfunction "1_1") (pintype "passive"))
    )
    (net (code "39") (name "/L_R4") (class "Default")
      (node (ref "DD1") (pin "34") (pinfunction "PC5_34") (pintype "passive"))
      (node (ref "R19") (pin "1") (pinfunction "1_1") (pintype "passive"))
    )
    (net (code "40") (name "/L_RR1") (class "Default")
      (node (ref "R16") (pin "2") (pinfunction "2_2") (pintype "passive"))
      (node (ref "SB10") (pin "4") (pinfunction "4_4") (pintype "passive"))
      (node (ref "SB14") (pin "4") (pinfunction "4_4") (pintype "passive"))
      (node (ref "SB18") (pin "4") (pinfunction "4_4") (pintype "passive"))
      (node (ref "SB2") (pin "4") (pinfunction "4_4") (pintype "passive"))
      (node (ref "SB22") (pin "4") (pinfunction "4_4") (pintype "passive"))
      (node (ref "SB26") (pin "4") (pinfunction "4_4") (pintype "passive"))
      (node (ref "SB30") (pin "4") (pinfunction "4_4") (pintype "passive"))
      (node (ref "SB6") (pin "4") (pinfunction "4_4") (pintype "passive"))
    )
    (net (code "41") (name "/L_RR2") (class "Default")
      (node (ref "R17") (pin "2") (pinfunction "2_2") (pintype "passive"))
      (node (ref "SB11") (pin "4") (pinfunction "4_4") (pintype "passive"))
      (node (ref "SB15") (pin "4") (pinfunction "4_4") (pintype "passive"))
      (node (ref "SB19") (pin "4") (pinfunction "4_4") (pintype "passive"))
      (node (ref "SB23") (pin "4") (pinfunction "4_4") (pintype "passive"))
      (node (ref "SB27") (pin "4") (pinfunction "4_4") (pintype "passive"))
      (node (ref "SB3") (pin "4") (pinfunction "4_4") (pintype "passive"))
      (node (ref "SB31") (pin "4") (pinfunction "4_4") (pintype "passive"))
      (node (ref "SB7") (pin "4") (pinfunction "4_4") (pintype "passive"))
    )
    (net (code "42") (name "/L_RR3") (class "Default")
      (node (ref "R18") (pin "2") (pinfunction "2_2") (pintype "passive"))
      (node (ref "SB12") (pin "4") (pinfunction "4_4") (pintype "passive"))
      (node (ref "SB16") (pin "4") (pinfunction "4_4") (pintype "passive"))
      (node (ref "SB20") (pin "4") (pinfunction "4_4") (pintype "passive"))
      (node (ref "SB24") (pin "4") (pinfunction "4_4") (pintype "passive"))
      (node (ref "SB28") (pin "4") (pinfunction "4_4") (pintype "passive"))
      (node (ref "SB32") (pin "4") (pinfunction "4_4") (pintype "passive"))
      (node (ref "SB4") (pin "4") (pinfunction "4_4") (pintype "passive"))
      (node (ref "SB8") (pin "4") (pinfunction "4_4") (pintype "passive"))
    )
    (net (code "43") (name "/L_RR4") (class "Default")
      (node (ref "R19") (pin "2") (pinfunction "2_2") (pintype "passive"))
      (node (ref "SB13") (pin "4") (pinfunction "4_4") (pintype "passive"))
      (node (ref "SB17") (pin "4") (pinfunction "4_4") (pintype "passive"))
      (node (ref "SB21") (pin "4") (pinfunction "4_4") (pintype "passive"))
      (node (ref "SB25") (pin "4") (pinfunction "4_4") (pintype "passive"))
      (node (ref "SB29") (pin "4") (pinfunction "4_4") (pintype "passive"))
      (node (ref "SB33") (pin "4") (pinfunction "4_4") (pintype "passive"))
      (node (ref "SB5") (pin "4") (pinfunction "4_4") (pintype "passive"))
      (node (ref "SB9") (pin "4") (pinfunction "4_4") (pintype "passive"))
    )
    (net (code "44") (name "/MIC_ADC") (class "Default")
      (node (ref "DA3") (pin "6") (pinfunction "MICOUT_6") (pintype "passive"))
      (node (ref "DD1") (pin "23") (pinfunction "PA0/WKUP_23") (pintype "passive"))
    )
    (net (code "45") (name "/OSC_IN") (class "Default")
      (node (ref "C18") (pin "1") (pinfunction "1_1") (pintype "passive"))
      (node (ref "DD1") (pin "12") (pinfunction "PH0/OSC_IN_12") (pintype "passive"))
      (node (ref "ZQ1") (pin "3") (pinfunction "XO_3") (pintype "passive"))
    )
    (net (code "46") (name "/OSC_OUT") (class "Default")
      (node (ref "C23") (pin "1") (pinfunction "1_1") (pintype "passive"))
      (node (ref "DD1") (pin "13") (pinfunction "PH1/OSC_OUT_13") (pintype "passive"))
      (node (ref "ZQ1") (pin "1") (pinfunction "XI_1") (pintype "passive"))
    )
    (net (code "47") (name "/PWR_ON") (class "Default")
      (node (ref "DD1") (pin "4") (pinfunction "PE5_4") (pintype "passive"))
      (node (ref "VD2") (pin "A") (pinfunction "A_A") (pintype "passive"))
    )
    (net (code "48") (name "/SDIO_CLK") (class "Default")
      (node (ref "DD1") (pin "80") (pinfunction "PC12_80") (pintype "passive"))
      (node (ref "XS2") (pin "5") (pinfunction "5_5") (pintype "passive"))
    )
    (net (code "49") (name "/SDIO_CMD") (class "Default")
      (node (ref "DD1") (pin "83") (pinfunction "PD2_83") (pintype "passive"))
      (node (ref "R3") (pin "1") (pinfunction "1_1") (pintype "passive"))
      (node (ref "XS2") (pin "3") (pinfunction "3_3") (pintype "passive"))
    )
    (net (code "50") (name "/SDIO_D0") (class "Default")
      (node (ref "DD1") (pin "65") (pinfunction "PC8_65") (pintype "passive"))
      (node (ref "R4") (pin "1") (pinfunction "1_1") (pintype "passive"))
      (node (ref "XS2") (pin "7") (pinfunction "7_7") (pintype "passive"))
    )
    (net (code "51") (name "/SDIO_D1") (class "Default")
      (node (ref "DD1") (pin "66") (pinfunction "PC9_66") (pintype "passive"))
      (node (ref "R6") (pin "1") (pinfunction "1_1") (pintype "passive"))
      (node (ref "XS2") (pin "8") (pinfunction "8_8") (pintype "passive"))
    )
    (net (code "52") (name "/SDIO_D2") (class "Default")
      (node (ref "DD1") (pin "78") (pinfunction "PC10_78") (pintype "passive"))
      (node (ref "R1") (pin "1") (pinfunction "1_1") (pintype "passive"))
      (node (ref "XS2") (pin "1") (pinfunction "1_1") (pintype "passive"))
    )
    (net (code "53") (name "/SDIO_D3") (class "Default")
      (node (ref "DD1") (pin "79") (pinfunction "PC11_79") (pintype "passive"))
      (node (ref "R2") (pin "1") (pinfunction "1_1") (pintype "passive"))
      (node (ref "XS2") (pin "2") (pinfunction "2_2") (pintype "passive"))
    )
    (net (code "54") (name "/SD_DET") (class "Default")
      (node (ref "DD1") (pin "84") (pinfunction "PD3_84") (pintype "passive"))
      (node (ref "R5") (pin "1") (pinfunction "1_1") (pintype "passive"))
    )
    (net (code "55") (name "/SPEAKER_L") (class "Default")
      (node (ref "C39") (pin "2") (pinfunction "2_2") (pintype "passive"))
      (node (ref "C40") (pin "2") (pinfunction "2_2") (pintype "passive"))
      (node (ref "C42") (pin "1") (pinfunction "1_1") (pintype "passive"))
      (node (ref "C43") (pin "1") (pinfunction "1_1") (pintype "passive"))
      (node (ref "XP2") (pin "2") (pinfunction "2_2") (pintype "passive"))
      (node (ref "XP2") (pin "3") (pinfunction "3_3") (pintype "passive"))
    )
    (net (code "56") (name "/SWCLK") (class "Default")
      (node (ref "DD1") (pin "76") (pinfunction "PA14/JTCK/SWCLK_76") (pintype "passive"))
      (node (ref "XS1") (pin "1") (pinfunction "1_1") (pintype "passive"))
    )
    (net (code "57") (name "/SWDIO") (class "Default")
      (node (ref "DD1") (pin "72") (pinfunction "PA13/JTMS/SWDIO_72") (pintype "passive"))
      (node (ref "XS1") (pin "4") (pinfunction "4_4") (pintype "passive"))
    )
    (net (code "58") (name "/USB_N") (class "Default")
      (node (ref "DD1") (pin "70") (pinfunction "PA11_70") (pintype "passive"))
      (node (ref "VD7") (pin "4") (pinfunction "4_4") (pintype "passive"))
      (node (ref "XS3") (pin "A7") (pinfunction "D-_A7") (pintype "passive"))
      (node (ref "XS3") (pin "B7") (pinfunction "D-_B7") (pintype "passive"))
    )
    (net (code "59") (name "/USB_P") (class "Default")
      (node (ref "DD1") (pin "71") (pinfunction "PA12_71") (pintype "passive"))
      (node (ref "VD7") (pin "3") (pinfunction "3_3") (pintype "passive"))
      (node (ref "XS3") (pin "A6") (pinfunction "D+_A6") (pintype "passive"))
      (node (ref "XS3") (pin "B6") (pinfunction "D+_B6") (pintype "passive"))
    )
    (net (code "60") (name "/VCC3V3") (class "Default")
      (node (ref "C13") (pin "1") (pinfunction "1_1") (pintype "passive"))
      (node (ref "C15") (pin "1") (pinfunction "1_1") (pintype "passive"))
      (node (ref "C17") (pin "1") (pinfunction "1_1") (pintype "passive"))
      (node (ref "C20") (pin "1") (pinfunction "1_1") (pintype "passive"))
      (node (ref "C22") (pin "1") (pinfunction "1_1") (pintype "passive"))
      (node (ref "C24") (pin "1") (pinfunction "1_1") (pintype "passive"))
      (node (ref "C25") (pin "1") (pinfunction "1_1") (pintype "passive"))
      (node (ref "C26") (pin "1") (pinfunction "1_1") (pintype "passive"))
      (node (ref "C27") (pin "1") (pinfunction "1_1") (pintype "passive"))
      (node (ref "C28") (pin "1") (pinfunction "1_1") (pintype "passive"))
      (node (ref "C30") (pin "1") (pinfunction "1_1") (pintype "passive"))
      (node (ref "C36") (pin "1") (pinfunction "1_1") (pintype "passive"))
      (node (ref "DA2") (pin "12") (pinfunction "VOUT_12") (pintype "passive"))
      (node (ref "DA2") (pin "13") (pinfunction "VOUT_13") (pintype "passive"))
      (node (ref "DA2") (pin "14") (pinfunction "VOUT_14") (pintype "passive"))
      (node (ref "DA3") (pin "10") (pinfunction "GAIN_10") (pintype "passive"))
      (node (ref "DA3") (pin "2") (pinfunction "~{SHDN}_2") (pintype "passive"))
      (node (ref "DA3") (pin "5") (pinfunction "VDD_5") (pintype "passive"))
      (node (ref "DA4") (pin "5") (pinfunction "VDD_5") (pintype "passive"))
      (node (ref "DA5") (pin "2") (pinfunction "VCC_2") (pintype "passive"))
      (node (ref "DD1") (pin "100") (pinfunction "VDD_100") (pintype "passive"))
      (node (ref "DD1") (pin "11") (pinfunction "VDD_11") (pintype "passive"))
      (node (ref "DD1") (pin "19") (pinfunction "VDD_19") (pintype "passive"))
      (node (ref "DD1") (pin "28") (pinfunction "VDD_28") (pintype "passive"))
      (node (ref "DD1") (pin "50") (pinfunction "VDD_50") (pintype "passive"))
      (node (ref "DD1") (pin "6") (pinfunction "VBAT_6") (pintype "passive"))
      (node (ref "DD1") (pin "75") (pinfunction "VDD_75") (pintype "passive"))
      (node (ref "L1") (pin "2") (pinfunction "2_2") (pintype "passive"))
      (node (ref "R27") (pin "2") (pinfunction "2_2") (pintype "passive"))
      (node (ref "R29") (pin "2") (pinfunction "2_2") (pintype "passive"))
      (node (ref "R30") (pin "2") (pinfunction "2_2") (pintype "passive"))
      (node (ref "R41") (pin "1") (pinfunction "1_1") (pintype "passive"))
      (node (ref "R42") (pin "1") (pinfunction "1_1") (pintype "passive"))
      (node (ref "R43") (pin "1") (pinfunction "1_1") (pintype "passive"))
    )
    (net (code "61") (name "/VCC5V") (class "Default")
      (node (ref "C1") (pin "1") (pinfunction "1_1") (pintype "passive"))
      (node (ref "DA1") (pin "1") (pinfunction "USB_1") (pintype "passive"))
      (node (ref "VD7") (pin "2") (pinfunction "2_2") (pintype "passive"))
      (node (ref "XS3") (pin "A5") (pinfunction "CC1_A5") (pintype "passive"))
      (node (ref "XS3") (pin "B5") (pinfunction "CC2_B5") (pintype "passive"))
    )
    (net (code "62") (name "/nRST") (class "Default")
      (node (ref "DD1") (pin "14") (pinfunction "NRST_14") (pintype "passive"))
      (node (ref "XS1") (pin "5") (pinfunction "5_5") (pintype "passive"))
    )
    (net (code "63") (name "GND") (class "Default")
      (node (ref "B1") (pin "1") (pinfunction "1_1") (pintype "passive"))
      (node (ref "BM1") (pin "2") (pinfunction "2_2") (pintype "passive"))
      (node (ref "BR1") (pin "1") (pinfunction "1_1") (pintype "passive"))
      (node (ref "BR1") (pin "C1") (pinfunction "C1_C1") (pintype "passive"))
      (node (ref "C1") (pin "2") (pinfunction "2_2") (pintype "passive"))
      (node (ref "C10") (pin "2") (pinfunction "2_2") (pintype "passive"))
      (node (ref "C11") (pin "2") (pinfunction "2_2") (pintype "passive"))
      (node (ref "C12") (pin "2") (pinfunction "2_2") (pintype "passive"))
      (node (ref "C13") (pin "2") (pinfunction "2_2") (pintype "passive"))
      (node (ref "C14") (pin "2") (pinfunction "2_2") (pintype "passive"))
      (node (ref "C15") (pin "2") (pinfunction "2_2") (pintype "passive"))
      (node (ref "C16") (pin "2") (pinfunction "2_2") (pintype "passive"))
      (node (ref "C17") (pin "2") (pinfunction "2_2") (pintype "passive"))
      (node (ref "C18") (pin "2") (pinfunction "2_2") (pintype "passive"))
      (node (ref "C19") (pin "2") (pinfunction "2_2") (pintype "passive"))
      (node (ref "C2") (pin "2") (pinfunction "2_2") (pintype "passive"))
      (node (ref "C20") (pin "2") (pinfunction "2_2") (pintype "passive"))
      (node (ref "C21") (pin "2") (pinfunction "2_2") (pintype "passive"))
      (node (ref "C22") (pin "2") (pinfunction "2_2") (pintype "passive"))
      (node (ref "C23") (pin "2") (pinfunction "2_2") (pintype "passive"))
      (node (ref "C24") (pin "2") (pinfunction "2_2") (pintype "passive"))
      (node (ref "C25") (pin "2") (pinfunction "2_2") (pintype "passive"))
      (node (ref "C26") (pin "2") (pinfunction "2_2") (pintype "passive"))
      (node (ref "C27") (pin "2") (pinfunction "2_2") (pintype "passive"))
      (node (ref "C28") (pin "2") (pinfunction "2_2") (pintype "passive"))
      (node (ref "C29") (pin "2") (pinfunction "2_2") (pintype "passive"))
      (node (ref "C3") (pin "2") (pinfunction "2_2") (pintype "passive"))
      (node (ref "C30") (pin "2") (pinfunction "2_2") (pintype "passive"))
      (node (ref "C31") (pin "2") (pinfunction "2_2") (pintype "passive"))
      (node (ref "C33") (pin "2") (pinfunction "2_2") (pintype "passive"))
      (node (ref "C34") (pin "2") (pinfunction "2_2") (pintype "passive"))
      (node (ref "C35") (pin "2") (pinfunction "2_2") (pintype "passive"))
      (node (ref "C36") (pin "2") (pinfunction "2_2") (pintype "passive"))
      (node (ref "C37") (pin "2") (pinfunction "2_2") (pintype "passive"))
      (node (ref "C38") (pin "2") (pinfunction "2_2") (pintype "passive"))
      (node (ref "C4") (pin "2") (pinfunction "2_2") (pintype "passive"))
      (node (ref "C41") (pin "2") (pinfunction "2_2") (pintype "passive"))
      (node (ref "C5") (pin "2") (pinfunction "2_2") (pintype "passive"))
      (node (ref "C6") (pin "2") (pinfunction "2_2") (pintype "passive"))
      (node (ref "C7") (pin "2") (pinfunction "2_2") (pintype "passive"))
      (node (ref "C8") (pin "2") (pinfunction "2_2") (pintype "passive"))
      (node (ref "C9") (pin "2") (pinfunction "2_2") (pintype "passive"))
      (node (ref "DA1") (pin "2") (pinfunction "GND_2") (pintype "passive"))
      (node (ref "DA2") (pin "10") (pinfunction "MODE_10") (pintype "passive"))
      (node (ref "DA2") (pin "2") (pinfunction "PGND_2") (pintype "passive"))
      (node (ref "DA2") (pin "9") (pinfunction "GND_9") (pintype "passive"))
      (node (ref "DA3") (pin "7") (pinfunction "GND_7") (pintype "passive"))
      (node (ref "DA3") (pin "9") (pinfunction "A/R_9") (pintype "passive"))
      (node (ref "DA4") (pin "1") (pinfunction "B1_1") (pintype "passive"))
      (node (ref "DA4") (pin "4") (pinfunction "GND_4") (pintype "passive"))
      (node (ref "DA4") (pin "9") (pinfunction "B2_9") (pintype "passive"))
      (node (ref "DA5") (pin "4") (pinfunction "GND_4") (pintype "passive"))
      (node (ref "DD1") (pin "10") (pinfunction "VSS_10") (pintype "passive"))
      (node (ref "DD1") (pin "20") (pinfunction "VSSA_20") (pintype "passive"))
      (node (ref "DD1") (pin "27") (pinfunction "VSS_27") (pintype "passive"))
      (node (ref "DD1") (pin "74") (pinfunction "VSS_74") (pintype "passive"))
      (node (ref "DD1") (pin "94") (pinfunction "BOOT0_94") (pintype "passive"))
      (node (ref "DD1") (pin "99") (pinfunction "VSS_99") (pintype "passive"))
      (node (ref "R10") (pin "1") (pinfunction "1_1") (pintype "passive"))
      (node (ref "R11") (pin "1") (pinfunction "1_1") (pintype "passive"))
      (node (ref "R13") (pin "1") (pinfunction "1_1") (pintype "passive"))
      (node (ref "R28") (pin "1") (pinfunction "1_1") (pintype "passive"))
      (node (ref "R31") (pin "2") (pinfunction "2_2") (pintype "passive"))
      (node (ref "R33") (pin "1") (pinfunction "1_1") (pintype "passive"))
      (node (ref "R35") (pin "2") (pinfunction "2_2") (pintype "passive"))
      (node (ref "R36") (pin "1") (pinfunction "1_1") (pintype "passive"))
      (node (ref "R40") (pin "1") (pinfunction "1_1") (pintype "passive"))
      (node (ref "VD7") (pin "1") (pinfunction "1_1") (pintype "passive"))
      (node (ref "VT1") (pin "2") (pinfunction "E_2") (pintype "passive"))
      (node (ref "XP1") (pin "1") (pinfunction "1_1") (pintype "passive"))
      (node (ref "XP2") (pin "1") (pinfunction "1_1") (pintype "passive"))
      (node (ref "XS1") (pin "3") (pinfunction "3_3") (pintype "passive"))
      (node (ref "XS2") (pin "0") (pinfunction "0_0") (pintype "passive"))
      (node (ref "XS2") (pin "6") (pinfunction "6_6") (pintype "passive"))
      (node (ref "XS3") (pin "A1") (pinfunction "GND_A1") (pintype "passive"))
      (node (ref "XS3") (pin "A12") (pinfunction "GND_A12") (pintype "passive"))
      (node (ref "XS3") (pin "B1") (pinfunction "GND_B1") (pintype "passive"))
      (node (ref "XS3") (pin "B12") (pinfunction "GND_B12") (pintype "passive"))
      (node (ref "XS3") (pin "SHIELD") (pinfunction "SHIELD_SHIELD") (pintype "passive"))
    )
    (net (code "64") (name "Net-(B1-Pad2)") (class "Default")
      (node (ref "B1") (pin "2") (pinfunction "2_2") (pintype "passive"))
      (node (ref "XP2") (pin "4") (pinfunction "4_4") (pintype "passive"))
    )
    (net (code "65") (name "Net-(BM1-Pad1)") (class "Default")
      (node (ref "BM1") (pin "1") (pinfunction "1_1") (pintype "passive"))
      (node (ref "C32") (pin "1") (pinfunction "1_1") (pintype "passive"))
      (node (ref "R34") (pin "2") (pinfunction "2_2") (pintype "passive"))
    )
    (net (code "66") (name "Net-(BR1-Pad2)") (class "Default")
      (node (ref "BR1") (pin "2") (pinfunction "2_2") (pintype "passive"))
      (node (ref "R39") (pin "2") (pinfunction "2_2") (pintype "passive"))
      (node (ref "R43") (pin "2") (pinfunction "2_2") (pintype "passive"))
      (node (ref "VD10") (pin "A") (pinfunction "A_A") (pintype "passive"))
    )
    (net (code "67") (name "Net-(BR1-PadA1)") (class "Default")
      (node (ref "BR1") (pin "A1") (pinfunction "A1_A1") (pintype "passive"))
      (node (ref "R37") (pin "2") (pinfunction "2_2") (pintype "passive"))
      (node (ref "R41") (pin "2") (pinfunction "2_2") (pintype "passive"))
      (node (ref "VD8") (pin "A") (pinfunction "A_A") (pintype "passive"))
    )
    (net (code "68") (name "Net-(BR1-PadB1)") (class "Default")
      (node (ref "BR1") (pin "B1") (pinfunction "B1_B1") (pintype "passive"))
      (node (ref "R38") (pin "2") (pinfunction "2_2") (pintype "passive"))
      (node (ref "R42") (pin "2") (pinfunction "2_2") (pintype "passive"))
      (node (ref "VD9") (pin "A") (pinfunction "A_A") (pintype "passive"))
    )
    (net (code "69") (name "Net-(C42-Pad2)") (class "Default")
      (node (ref "C42") (pin "2") (pinfunction "2_2") (pintype "passive"))
      (node (ref "R36") (pin "2") (pinfunction "2_2") (pintype "passive"))
    )
    (net (code "70") (name "Net-(C43-Pad2)") (class "Default")
      (node (ref "C43") (pin "2") (pinfunction "2_2") (pintype "passive"))
      (node (ref "R40") (pin "2") (pinfunction "2_2") (pintype "passive"))
    )
    (net (code "71") (name "Net-(DA1-~{CHG})") (class "Default")
      (node (ref "DA1") (pin "3") (pinfunction "~{CHG}_3") (pintype "passive"))
      (node (ref "R7") (pin "2") (pinfunction "2_2") (pintype "passive"))
    )
    (net (code "72") (name "Net-(DA2-EN)") (class "Default")
      (node (ref "C10") (pin "1") (pinfunction "1_1") (pintype "passive"))
      (node (ref "DA2") (pin "4") (pinfunction "VIN_4") (pintype "passive"))
      (node (ref "DA2") (pin "5") (pinfunction "VIN_5") (pintype "passive"))
      (node (ref "DA2") (pin "6") (pinfunction "VIN_6") (pintype "passive"))
      (node (ref "DA2") (pin "7") (pinfunction "VINA_7") (pintype "passive"))
      (node (ref "DA2") (pin "8") (pinfunction "EN_8") (pintype "passive"))
      (node (ref "VT2") (pin "3") (pinfunction "3_3") (pintype "passive"))
    )
    (net (code "73") (name "Net-(DA2-FB)") (class "Default")
      (node (ref "DA2") (pin "11") (pinfunction "FB_11") (pintype "passive"))
      (node (ref "R27") (pin "1") (pinfunction "1_1") (pintype "passive"))
      (node (ref "R28") (pin "2") (pinfunction "2_2") (pintype "passive"))
    )
    (net (code "74") (name "Net-(DA2-L1)") (class "Default")
      (node (ref "DA2") (pin "3") (pinfunction "L1_3") (pintype "passive"))
      (node (ref "L2") (pin "1") (pinfunction "1_1") (pintype "passive"))
    )
    (net (code "75") (name "Net-(DA2-L2)") (class "Default")
      (node (ref "DA2") (pin "1") (pinfunction "L2_1") (pintype "passive"))
      (node (ref "L2") (pin "2") (pinfunction "2_2") (pintype "passive"))
    )
    (net (code "76") (name "Net-(DA3-BIAS)") (class "Default")
      (node (ref "C29") (pin "1") (pinfunction "1_1") (pintype "passive"))
      (node (ref "DA3") (pin "12") (pinfunction "BIAS_12") (pintype "passive"))
    )
    (net (code "77") (name "Net-(DA3-CG)") (class "Default")
      (node (ref "C31") (pin "1") (pinfunction "1_1") (pintype "passive"))
      (node (ref "DA3") (pin "3") (pinfunction "CG_3") (pintype "passive"))
    )
    (net (code "78") (name "Net-(DA3-CT)") (class "Default")
      (node (ref "C33") (pin "1") (pinfunction "1_1") (pintype "passive"))
      (node (ref "DA3") (pin "1") (pinfunction "CT_1") (pintype "passive"))
    )
    (net (code "79") (name "Net-(DA3-MICBIAS)") (class "Default")
      (node (ref "DA3") (pin "13") (pinfunction "MICBIAS_13") (pintype "passive"))
      (node (ref "R32") (pin "1") (pinfunction "1_1") (pintype "passive"))
      (node (ref "R34") (pin "1") (pinfunction "1_1") (pintype "passive"))
    )
    (net (code "80") (name "Net-(DA3-MICIN)") (class "Default")
      (node (ref "C32") (pin "2") (pinfunction "2_2") (pintype "passive"))
      (node (ref "DA3") (pin "8") (pinfunction "MICIN_8") (pintype "passive"))
    )
    (net (code "81") (name "Net-(DA3-TH)") (class "Default")
      (node (ref "DA3") (pin "14") (pinfunction "TH_14") (pintype "passive"))
      (node (ref "R32") (pin "2") (pinfunction "2_2") (pintype "passive"))
      (node (ref "R33") (pin "2") (pinfunction "2_2") (pintype "passive"))
    )
    (net (code "82") (name "Net-(DA4-W1)") (class "Default")
      (node (ref "DA4") (pin "10") (pinfunction "W1_10") (pintype "passive"))
      (node (ref "DA5") (pin "7") (pinfunction "IN1+_7") (pintype "passive"))
      (node (ref "R31") (pin "1") (pinfunction "1_1") (pintype "passive"))
    )
    (net (code "83") (name "Net-(DA4-W2)") (class "Default")
      (node (ref "DA4") (pin "3") (pinfunction "W2_3") (pintype "passive"))
      (node (ref "DA5") (pin "6") (pinfunction "IN2+_6") (pintype "passive"))
      (node (ref "R35") (pin "1") (pinfunction "1_1") (pintype "passive"))
    )
    (net (code "84") (name "Net-(DA5-IN1-)") (class "Default")
      (node (ref "C34") (pin "1") (pinfunction "1_1") (pintype "passive"))
      (node (ref "DA5") (pin "8") (pinfunction "IN1-_8") (pintype "passive"))
    )
    (net (code "85") (name "Net-(DA5-IN2-)") (class "Default")
      (node (ref "C35") (pin "1") (pinfunction "1_1") (pintype "passive"))
      (node (ref "DA5") (pin "5") (pinfunction "IN2-_5") (pintype "passive"))
    )
    (net (code "86") (name "Net-(DA5-OUT1)") (class "Default")
      (node (ref "C39") (pin "1") (pinfunction "1_1") (pintype "passive"))
      (node (ref "DA5") (pin "1") (pinfunction "OUT1_1") (pintype "passive"))
    )
    (net (code "87") (name "Net-(DA5-OUT2)") (class "Default")
      (node (ref "C40") (pin "1") (pinfunction "1_1") (pintype "passive"))
      (node (ref "DA5") (pin "3") (pinfunction "OUT2_3") (pintype "passive"))
    )
    (net (code "88") (name "Net-(DD1-PC6)") (class "Default")
      (node (ref "C4") (pin "1") (pinfunction "1_1") (pintype "passive"))
      (node (ref "DD1") (pin "63") (pinfunction "PC6_63") (pintype "passive"))
      (node (ref "R8") (pin "2") (pinfunction "2_2") (pintype "passive"))
    )
    (net (code "89") (name "Net-(DD1-PD9)") (class "Default")
      (node (ref "C5") (pin "1") (pinfunction "1_1") (pintype "passive"))
      (node (ref "DD1") (pin "56") (pinfunction "PD9_56") (pintype "passive"))
      (node (ref "R20") (pin "2") (pinfunction "2_2") (pintype "passive"))
    )
    (net (code "90") (name "Net-(DD1-PD10)") (class "Default")
      (node (ref "C8") (pin "1") (pinfunction "1_1") (pintype "passive"))
      (node (ref "DD1") (pin "57") (pinfunction "PD10_57") (pintype "passive"))
      (node (ref "R21") (pin "2") (pinfunction "2_2") (pintype "passive"))
    )
    (net (code "91") (name "Net-(DD1-PD11)") (class "Default")
      (node (ref "C12") (pin "1") (pinfunction "1_1") (pintype "passive"))
      (node (ref "DD1") (pin "58") (pinfunction "PD11_58") (pintype "passive"))
      (node (ref "R22") (pin "2") (pinfunction "2_2") (pintype "passive"))
    )
    (net (code "92") (name "Net-(DD1-PD12)") (class "Default")
      (node (ref "C14") (pin "1") (pinfunction "1_1") (pintype "passive"))
      (node (ref "DD1") (pin "59") (pinfunction "PD12_59") (pintype "passive"))
      (node (ref "R23") (pin "2") (pinfunction "2_2") (pintype "passive"))
    )
    (net (code "93") (name "Net-(DD1-PD13)") (class "Default")
      (node (ref "C16") (pin "1") (pinfunction "1_1") (pintype "passive"))
      (node (ref "DD1") (pin "60") (pinfunction "PD13_60") (pintype "passive"))
      (node (ref "R24") (pin "2") (pinfunction "2_2") (pintype "passive"))
    )
    (net (code "94") (name "Net-(DD1-PD14)") (class "Default")
      (node (ref "C19") (pin "1") (pinfunction "1_1") (pintype "passive"))
      (node (ref "DD1") (pin "61") (pinfunction "PD14_61") (pintype "passive"))
      (node (ref "R25") (pin "2") (pinfunction "2_2") (pintype "passive"))
    )
    (net (code "95") (name "Net-(DD1-PD15)") (class "Default")
      (node (ref "C21") (pin "1") (pinfunction "1_1") (pintype "passive"))
      (node (ref "DD1") (pin "62") (pinfunction "PD15_62") (pintype "passive"))
      (node (ref "R26") (pin "2") (pinfunction "2_2") (pintype "passive"))
    )
    (net (code "96") (name "Net-(DD1-VCAP1)") (class "Default")
      (node (ref "C11") (pin "1") (pinfunction "1_1") (pintype "passive"))
      (node (ref "DD1") (pin "49") (pinfunction "VCAP1_49") (pintype "passive"))
    )
    (net (code "97") (name "Net-(DD1-VCAP2)") (class "Default")
      (node (ref "C7") (pin "1") (pinfunction "1_1") (pintype "passive"))
      (node (ref "DD1") (pin "73") (pinfunction "VCAP2_73") (pintype "passive"))
    )
    (net (code "98") (name "Net-(DD1-VDDA)") (class "Default")
      (node (ref "C6") (pin "1") (pinfunction "1_1") (pintype "passive"))
      (node (ref "C9") (pin "1") (pinfunction "1_1") (pintype "passive"))
      (node (ref "DD1") (pin "22") (pinfunction "VDDA_22") (pintype "passive"))
      (node (ref "L1") (pin "1") (pinfunction "1_1") (pintype "passive"))
    )
    (net (code "99") (name "Net-(R5-Pad2)") (class "Default")
      (node (ref "R5") (pin "2") (pinfunction "2_2") (pintype "passive"))
      (node (ref "XS2") (pin "9") (pinfunction "9_9") (pintype "passive"))
    )
    (net (code "100") (name "Net-(R11-Pad2)") (class "Default")
      (node (ref "R11") (pin "2") (pinfunction "2_2") (pintype "passive"))
      (node (ref "R12") (pin "2") (pinfunction "2_2") (pintype "passive"))
      (node (ref "SB1") (pin "1") (pinfunction "1_1") (pintype "passive"))
    )
    (net (code "101") (name "Net-(R12-Pad1)") (class "Default")
      (node (ref "R12") (pin "1") (pinfunction "1_1") (pintype "passive"))
      (node (ref "VD1") (pin "A") (pinfunction "A_A") (pintype "passive"))
    )
    (net (code "102") (name "Net-(R14-Pad2)") (class "Default")
      (node (ref "R14") (pin "2") (pinfunction "2_2") (pintype "passive"))
      (node (ref "VD2") (pin "C") (pinfunction "C_C") (pintype "passive"))
    )
    (net (code "103") (name "Net-(VT1-B)") (class "Default")
      (node (ref "R13") (pin "2") (pinfunction "2_2") (pintype "passive"))
      (node (ref "R14") (pin "1") (pinfunction "1_1") (pintype "passive"))
      (node (ref "VD1") (pin "C") (pinfunction "C_C") (pintype "passive"))
      (node (ref "VT1") (pin "1") (pinfunction "B_1") (pintype "passive"))
    )
    (net (code "104") (name "Net-(VT1-C)") (class "Default")
      (node (ref "R15") (pin "1") (pinfunction "1_1") (pintype "passive"))
      (node (ref "VT1") (pin "3") (pinfunction "C_3") (pintype "passive"))
      (node (ref "VT2") (pin "1") (pinfunction "1_1") (pintype "passive"))
    )
    (net (code "105") (name "unconnected-(DA1-DC-Pad4)") (class "Default")
      (node (ref "DA1") (pin "4") (pinfunction "DC_4") (pintype "passive"))
    )
    (net (code "106") (name "unconnected-(DD1-PA2-Pad25)") (class "Default")
      (node (ref "DD1") (pin "25") (pinfunction "PA2_25") (pintype "passive"))
    )
    (net (code "107") (name "unconnected-(DD1-PA3-Pad26)") (class "Default")
      (node (ref "DD1") (pin "26") (pinfunction "PA3_26") (pintype "passive"))
    )
    (net (code "108") (name "unconnected-(DD1-PA6-Pad31)") (class "Default")
      (node (ref "DD1") (pin "31") (pinfunction "PA6_31") (pintype "passive"))
    )
    (net (code "109") (name "unconnected-(DD1-PA7-Pad32)") (class "Default")
      (node (ref "DD1") (pin "32") (pinfunction "PA7_32") (pintype "passive"))
    )
    (net (code "110") (name "unconnected-(DD1-PA8-Pad67)") (class "Default")
      (node (ref "DD1") (pin "67") (pinfunction "PA8_67") (pintype "passive"))
    )
    (net (code "111") (name "unconnected-(DD1-PA9-Pad68)") (class "Default")
      (node (ref "DD1") (pin "68") (pinfunction "PA9_68") (pintype "passive"))
    )
    (net (code "112") (name "unconnected-(DD1-PA10-Pad69)") (class "Default")
      (node (ref "DD1") (pin "69") (pinfunction "PA10_69") (pintype "passive"))
    )
    (net (code "113") (name "unconnected-(DD1-PA15{slash}_JTDI-Pad77)") (class "Default")
      (node (ref "DD1") (pin "77") (pinfunction "PA15/_JTDI_77") (pintype "passive"))
    )
    (net (code "114") (name "unconnected-(DD1-PB3{slash}JTDO{slash}TRACESWO-Pad89)") (class "Default")
      (node (ref "DD1") (pin "89") (pinfunction "PB3/JTDO/TRACESWO_89") (pintype "passive"))
    )
    (net (code "115") (name "unconnected-(DD1-PB4{slash}JNTRST-Pad90)") (class "Default")
      (node (ref "DD1") (pin "90") (pinfunction "PB4/JNTRST_90") (pintype "passive"))
    )
    (net (code "116") (name "unconnected-(DD1-PB5-Pad91)") (class "Default")
      (node (ref "DD1") (pin "91") (pinfunction "PB5_91") (pintype "passive"))
    )
    (net (code "117") (name "unconnected-(DD1-PB8-Pad95)") (class "Default")
      (node (ref "DD1") (pin "95") (pinfunction "PB8_95") (pintype "passive"))
    )
    (net (code "118") (name "unconnected-(DD1-PB9-Pad96)") (class "Default")
      (node (ref "DD1") (pin "96") (pinfunction "PB9_96") (pintype "passive"))
    )
    (net (code "119") (name "unconnected-(DD1-PB12-Pad51)") (class "Default")
      (node (ref "DD1") (pin "51") (pinfunction "PB12_51") (pintype "passive"))
    )
    (net (code "120") (name "unconnected-(DD1-PC0-Pad15)") (class "Default")
      (node (ref "DD1") (pin "15") (pinfunction "PC0_15") (pintype "passive"))
    )
    (net (code "121") (name "unconnected-(DD1-PC1-Pad16)") (class "Default")
      (node (ref "DD1") (pin "16") (pinfunction "PC1_16") (pintype "passive"))
    )
    (net (code "122") (name "unconnected-(DD1-PC2-Pad17)") (class "Default")
      (node (ref "DD1") (pin "17") (pinfunction "PC2_17") (pintype "passive"))
    )
    (net (code "123") (name "unconnected-(DD1-PC3-Pad18)") (class "Default")
      (node (ref "DD1") (pin "18") (pinfunction "PC3_18") (pintype "passive"))
    )
    (net (code "124") (name "unconnected-(DD1-PC4-Pad33)") (class "Default")
      (node (ref "DD1") (pin "33") (pinfunction "PC4_33") (pintype "passive"))
    )
    (net (code "125") (name "unconnected-(DD1-PC7-Pad64)") (class "Default")
      (node (ref "DD1") (pin "64") (pinfunction "PC7_64") (pintype "passive"))
    )
    (net (code "126") (name "unconnected-(DD1-PC13-Pad7)") (class "Default")
      (node (ref "DD1") (pin "7") (pinfunction "PC13_7") (pintype "passive"))
    )
    (net (code "127") (name "unconnected-(DD1-PC14{slash}OSC32_IN-Pad8)") (class "Default")
      (node (ref "DD1") (pin "8") (pinfunction "PC14/OSC32_IN_8") (pintype "passive"))
    )
    (net (code "128") (name "unconnected-(DD1-PC15{slash}OSC32_OUT-Pad9)") (class "Default")
      (node (ref "DD1") (pin "9") (pinfunction "PC15/OSC32_OUT_9") (pintype "passive"))
    )
    (net (code "129") (name "unconnected-(DD1-PD0-Pad81)") (class "Default")
      (node (ref "DD1") (pin "81") (pinfunction "PD0_81") (pintype "passive"))
    )
    (net (code "130") (name "unconnected-(DD1-PD1-Pad82)") (class "Default")
      (node (ref "DD1") (pin "82") (pinfunction "PD1_82") (pintype "passive"))
    )
    (net (code "131") (name "unconnected-(DD1-PD4-Pad85)") (class "Default")
      (node (ref "DD1") (pin "85") (pinfunction "PD4_85") (pintype "passive"))
    )
    (net (code "132") (name "unconnected-(DD1-PD5-Pad86)") (class "Default")
      (node (ref "DD1") (pin "86") (pinfunction "PD5_86") (pintype "passive"))
    )
    (net (code "133") (name "unconnected-(DD1-PD6-Pad87)") (class "Default")
      (node (ref "DD1") (pin "87") (pinfunction "PD6_87") (pintype "passive"))
    )
    (net (code "134") (name "unconnected-(DD1-PD7-Pad88)") (class "Default")
      (node (ref "DD1") (pin "88") (pinfunction "PD7_88") (pintype "passive"))
    )
    (net (code "135") (name "unconnected-(DD1-PE0-Pad97)") (class "Default")
      (node (ref "DD1") (pin "97") (pinfunction "PE0_97") (pintype "passive"))
    )
    (net (code "136") (name "unconnected-(DD1-PE1-Pad98)") (class "Default")
      (node (ref "DD1") (pin "98") (pinfunction "PE1_98") (pintype "passive"))
    )
    (net (code "137") (name "unconnected-(DD1-PE2-Pad1)") (class "Default")
      (node (ref "DD1") (pin "1") (pinfunction "PE2_1") (pintype "passive"))
    )
    (net (code "138") (name "unconnected-(DD1-PE3-Pad2)") (class "Default")
      (node (ref "DD1") (pin "2") (pinfunction "PE3_2") (pintype "passive"))
    )
    (net (code "139") (name "unconnected-(DD1-PE6-Pad5)") (class "Default")
      (node (ref "DD1") (pin "5") (pinfunction "PE6_5") (pintype "passive"))
    )
    (net (code "140") (name "unconnected-(DD1-VREF+-Pad21)") (class "Default")
      (node (ref "DD1") (pin "21") (pinfunction "VREF+_21") (pintype "passive"))
    )
    (net (code "141") (name "unconnected-(ZQ1-NC-Pad2)") (class "Default")
      (node (ref "ZQ1") (pin "2") (pinfunction "NC_2") (pintype "passive"))
    )
    (net (code "142") (name "unconnected-(ZQ1-NC-Pad4)") (class "Default")
      (node (ref "ZQ1") (pin "4") (pinfunction "NC_4") (pintype "passive"))
    )
  )
)
